# radio_module.net
KiCad netlist of a schematic drawn in EAGLE
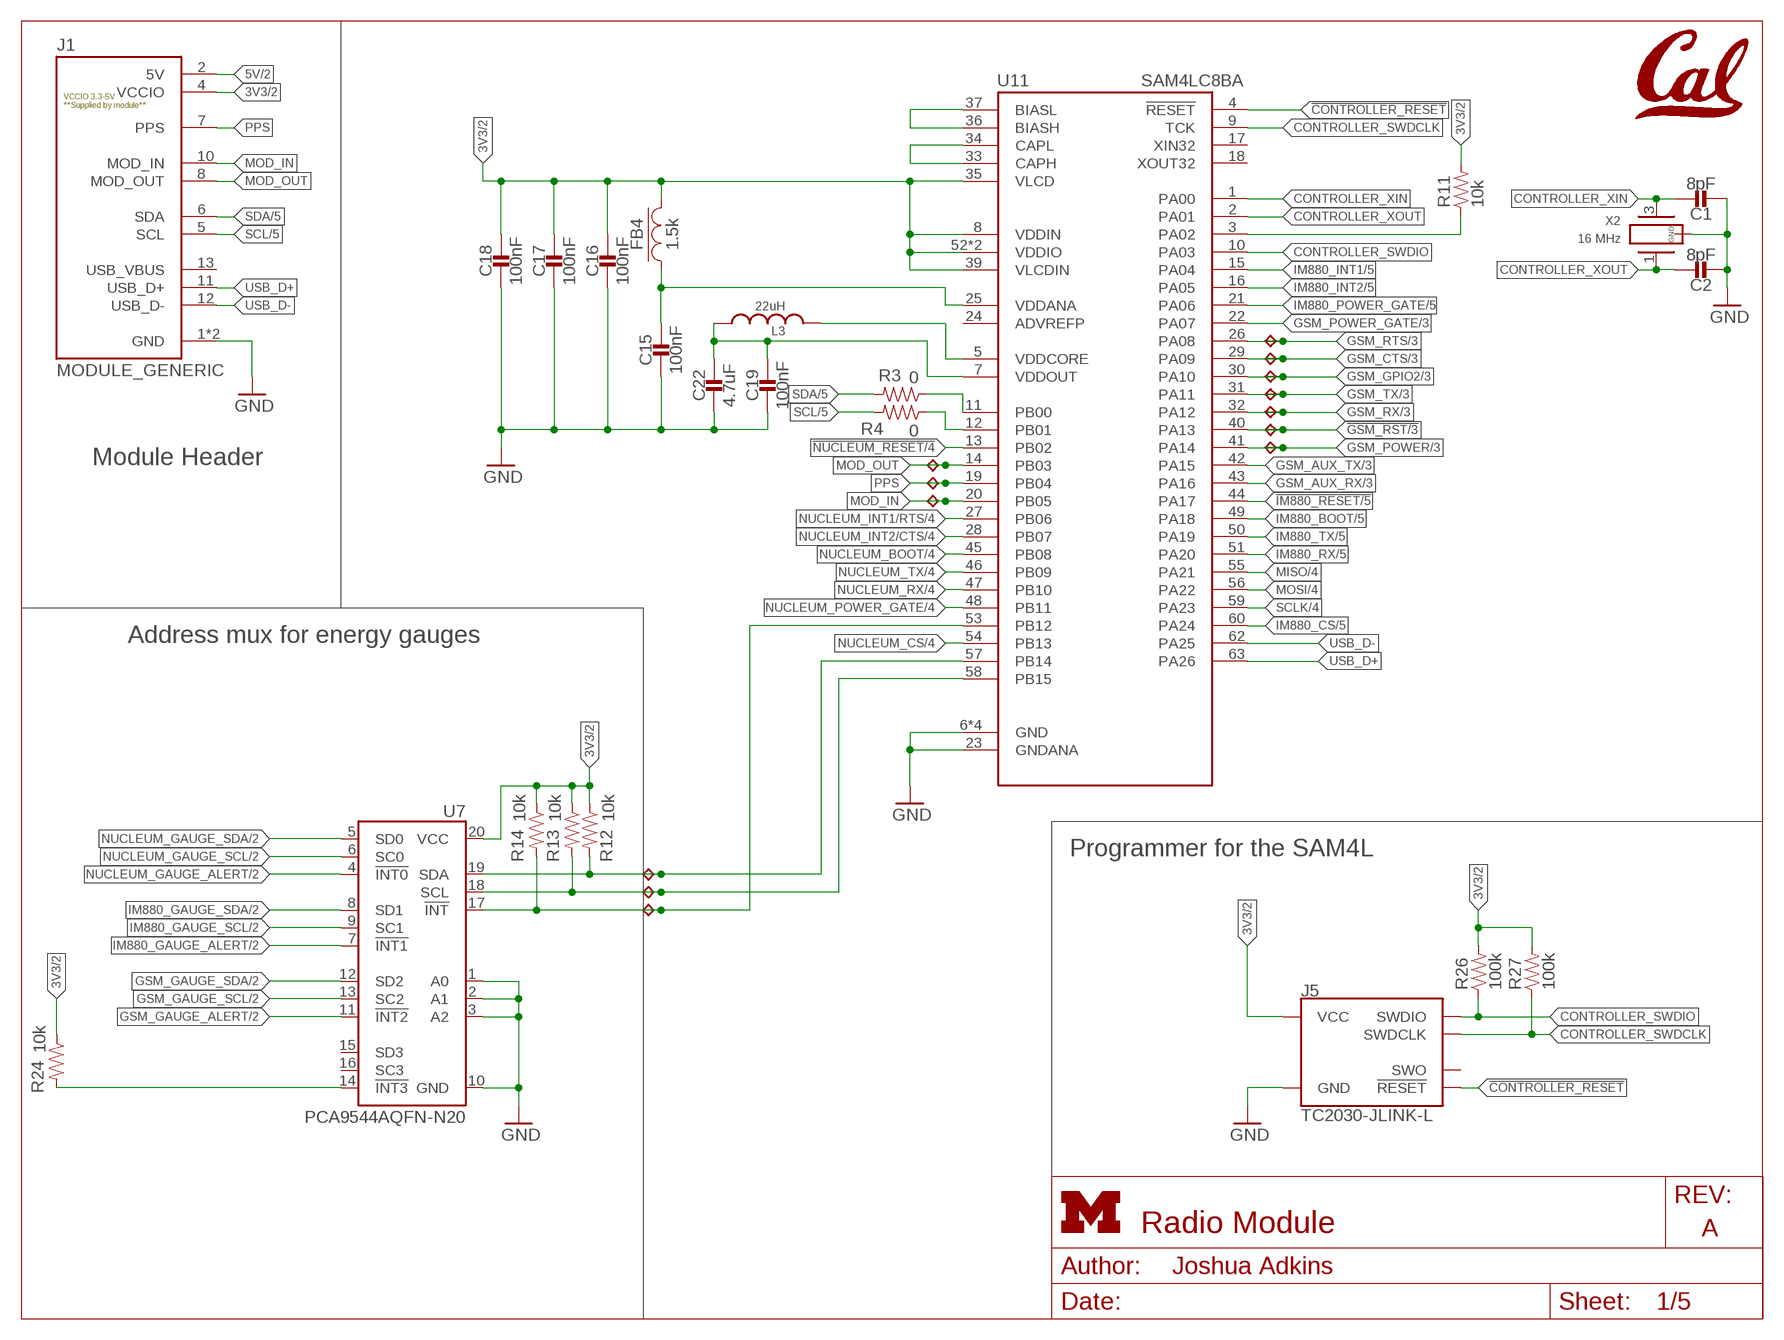
[diagram p0: schematic, sheet 1]
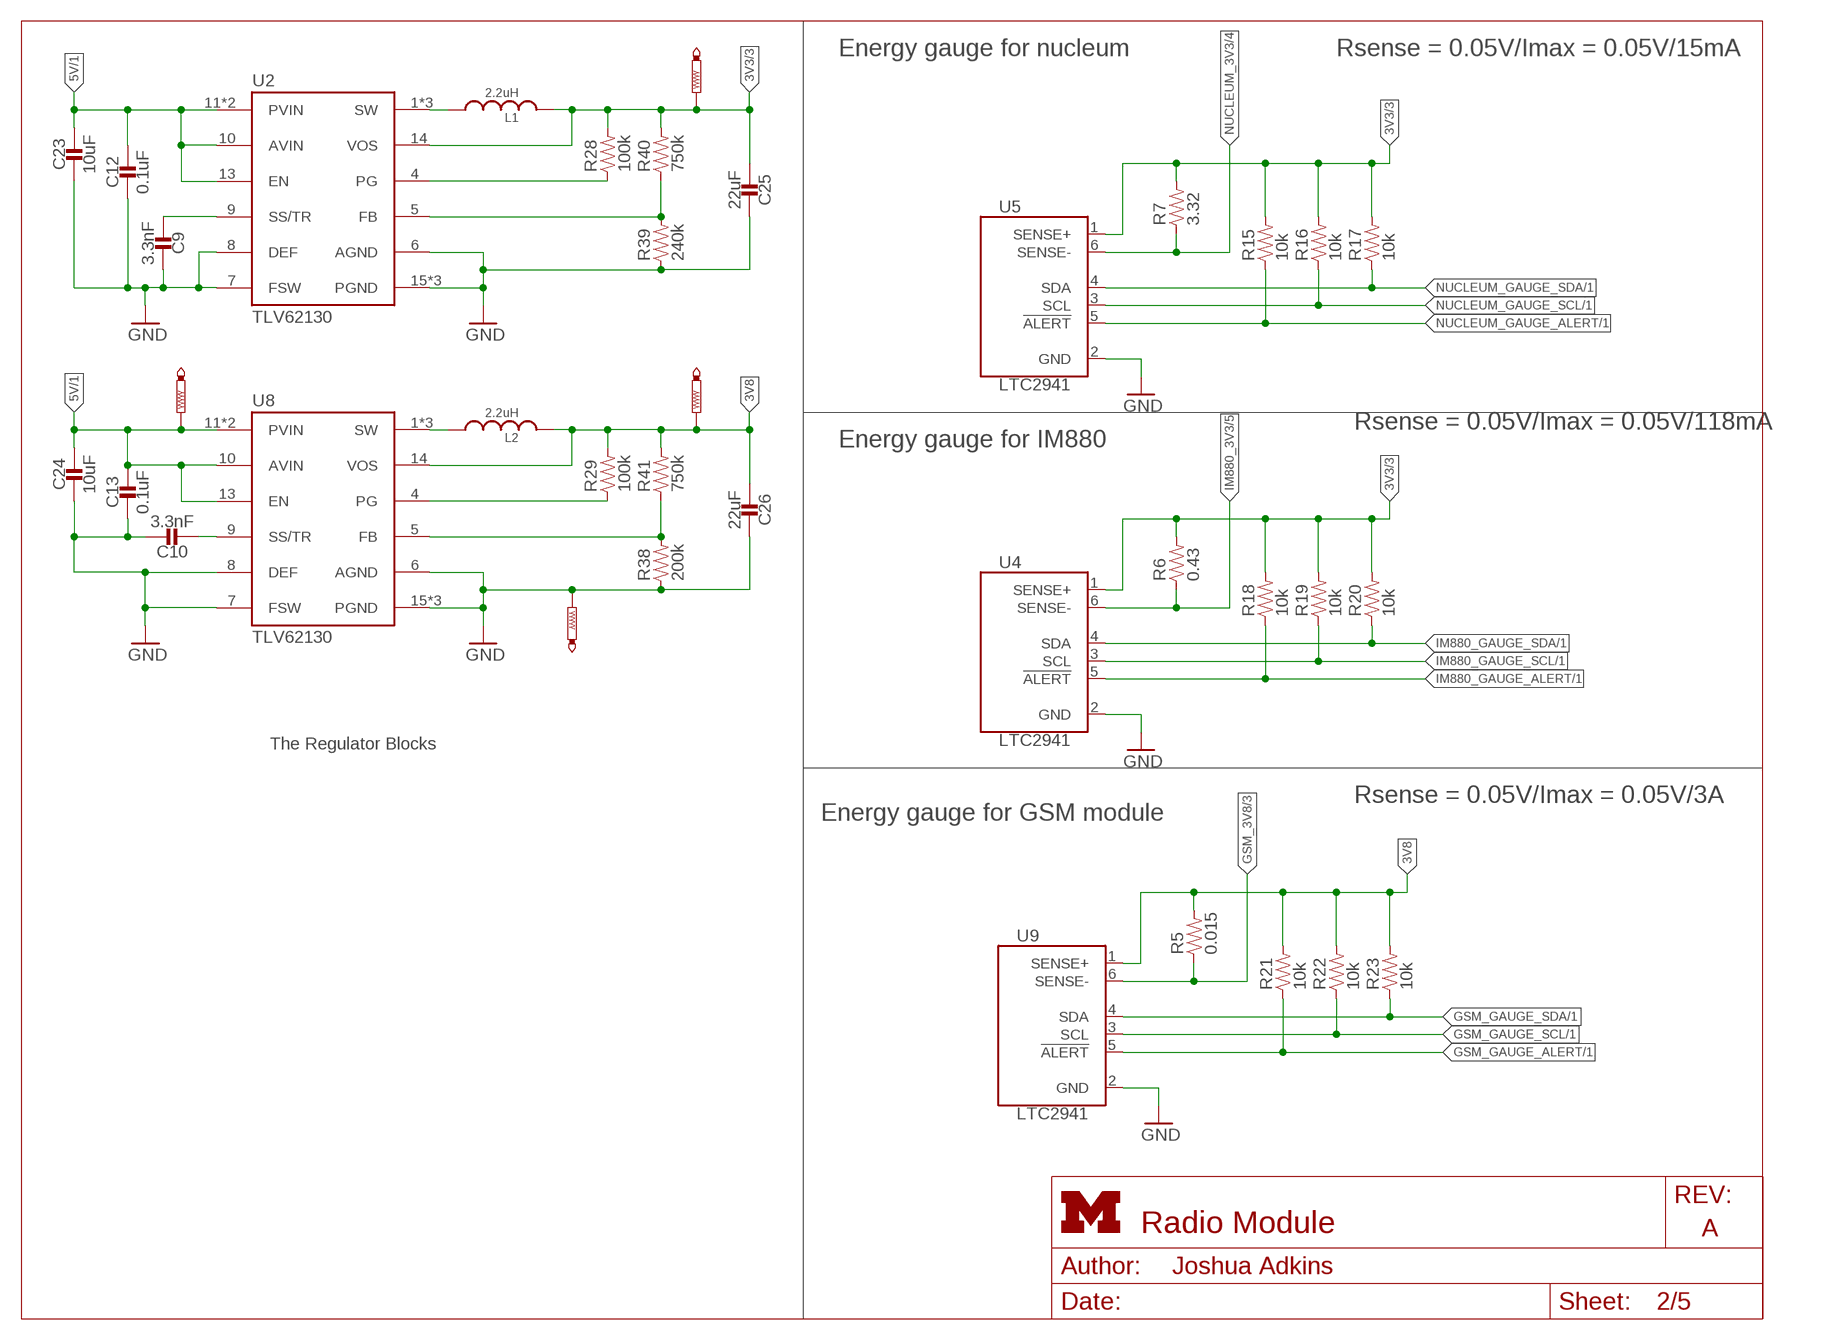
[diagram p1: schematic, sheet 2]
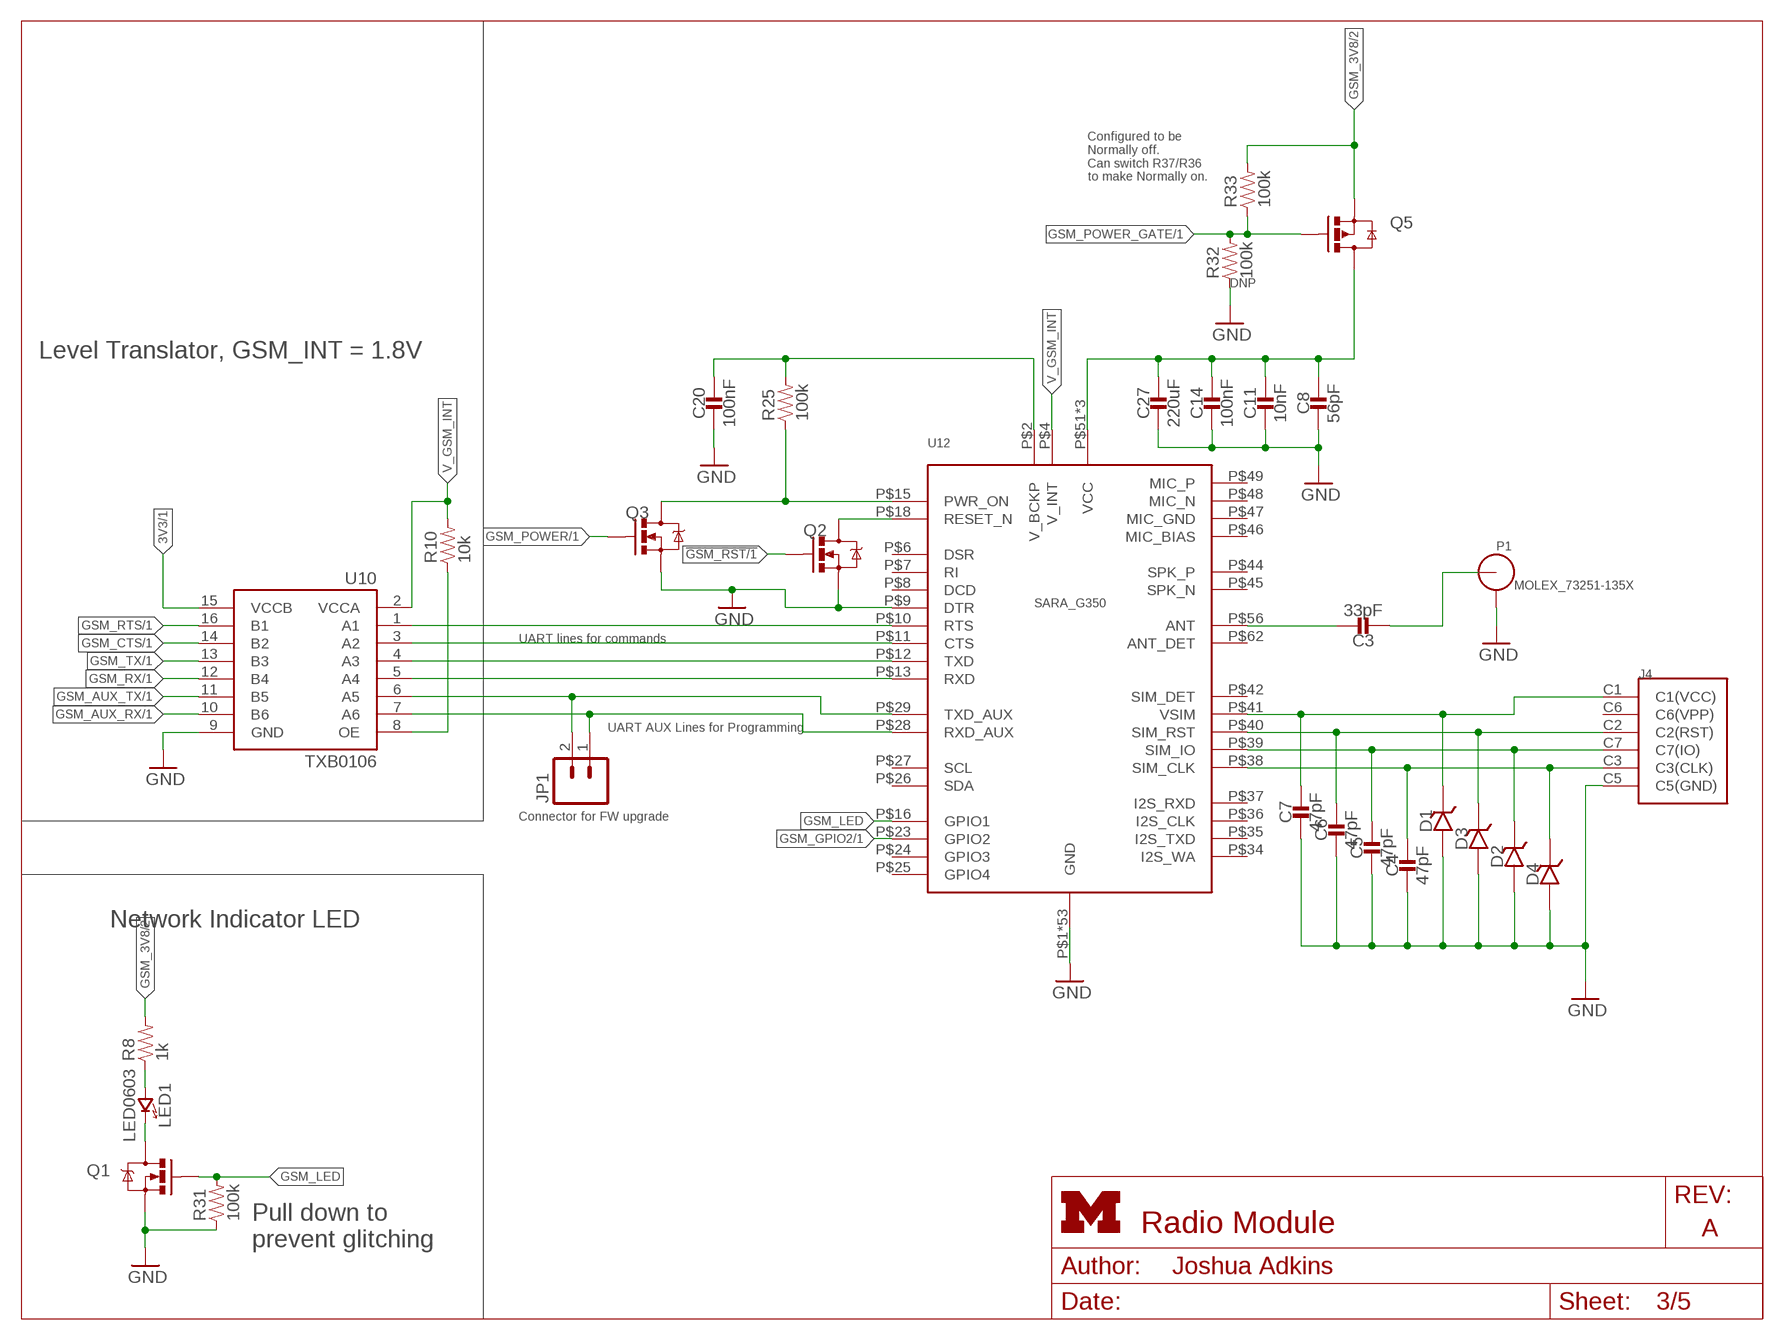
[diagram p2: schematic, sheet 3]
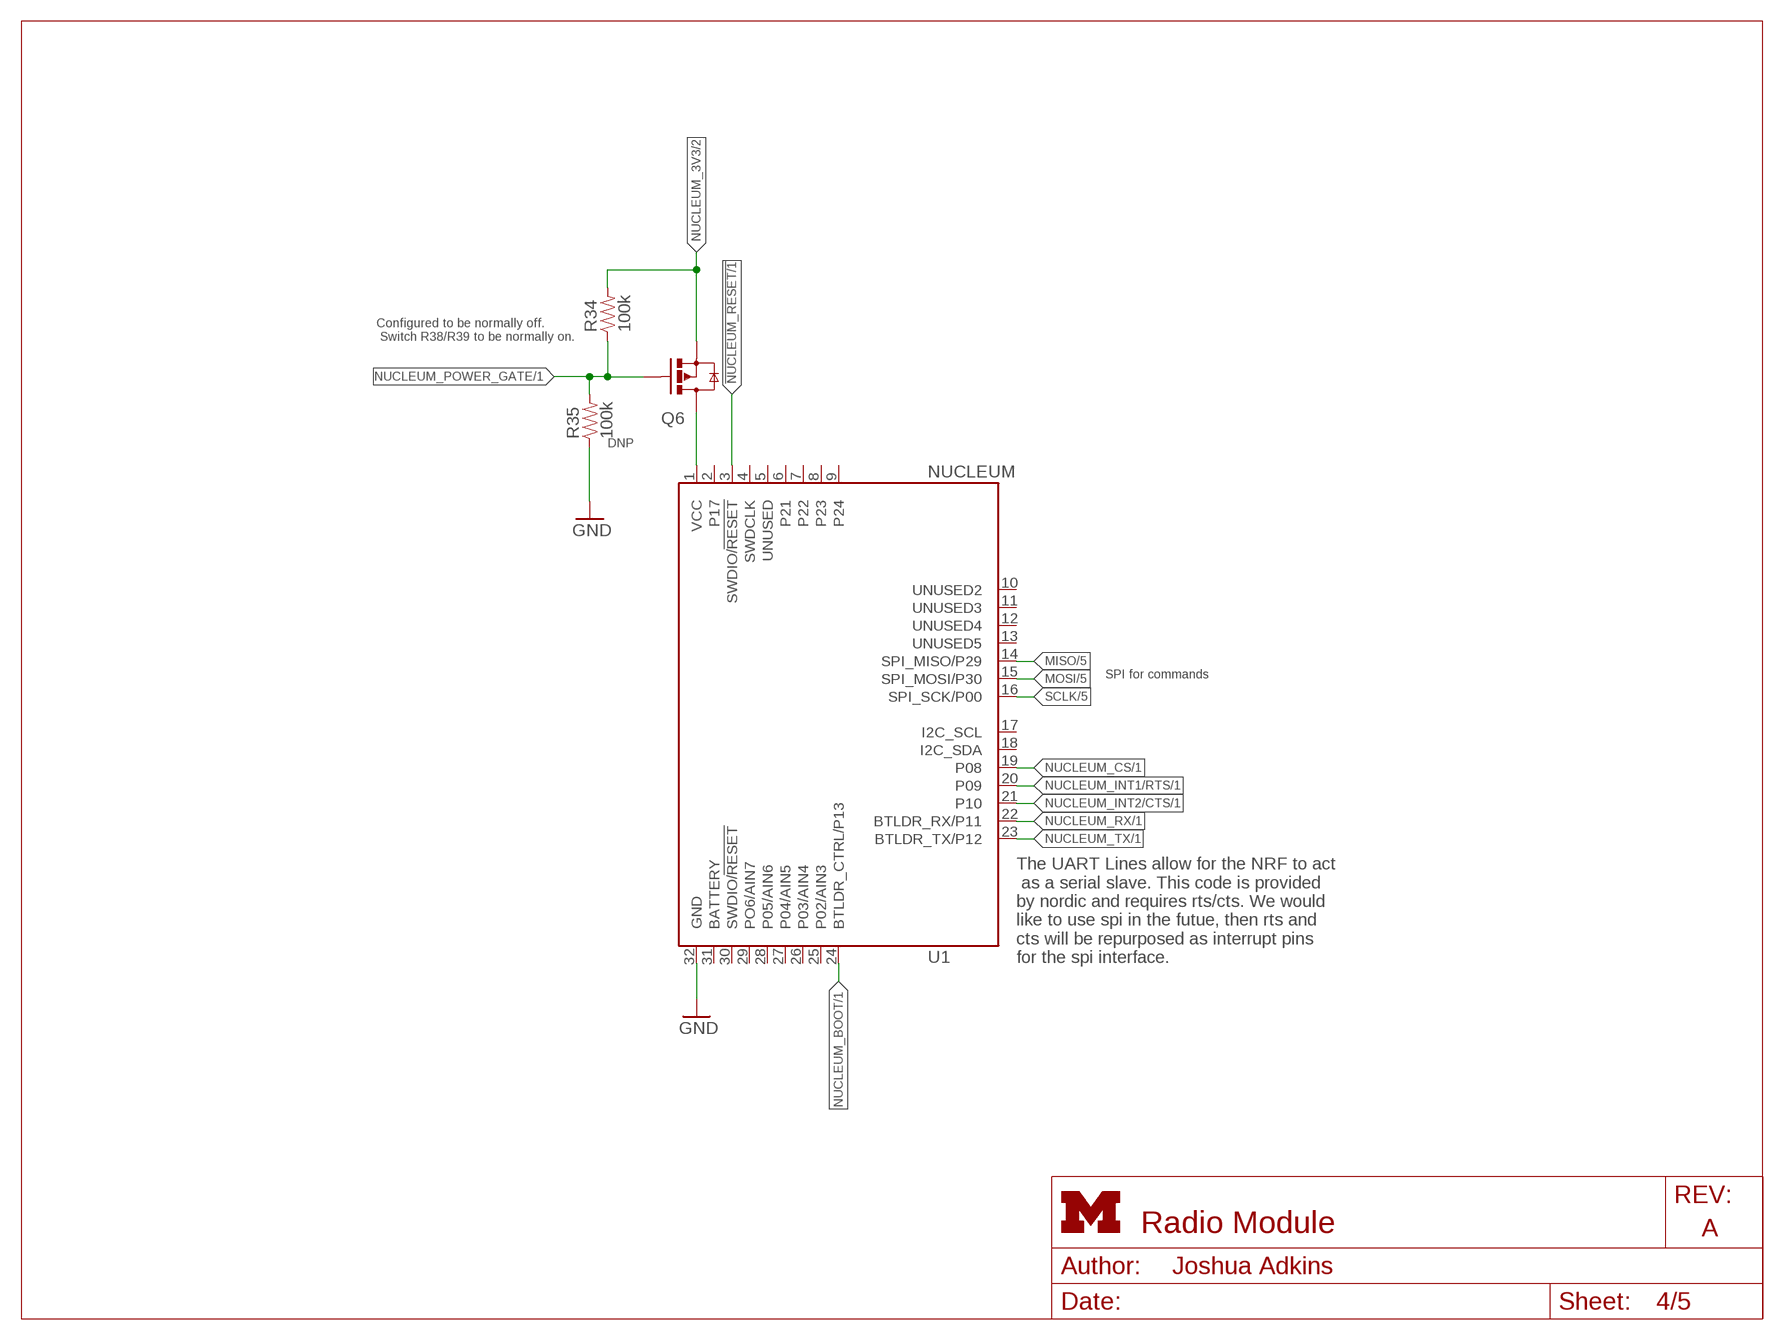
[diagram p3: schematic, sheet 4]
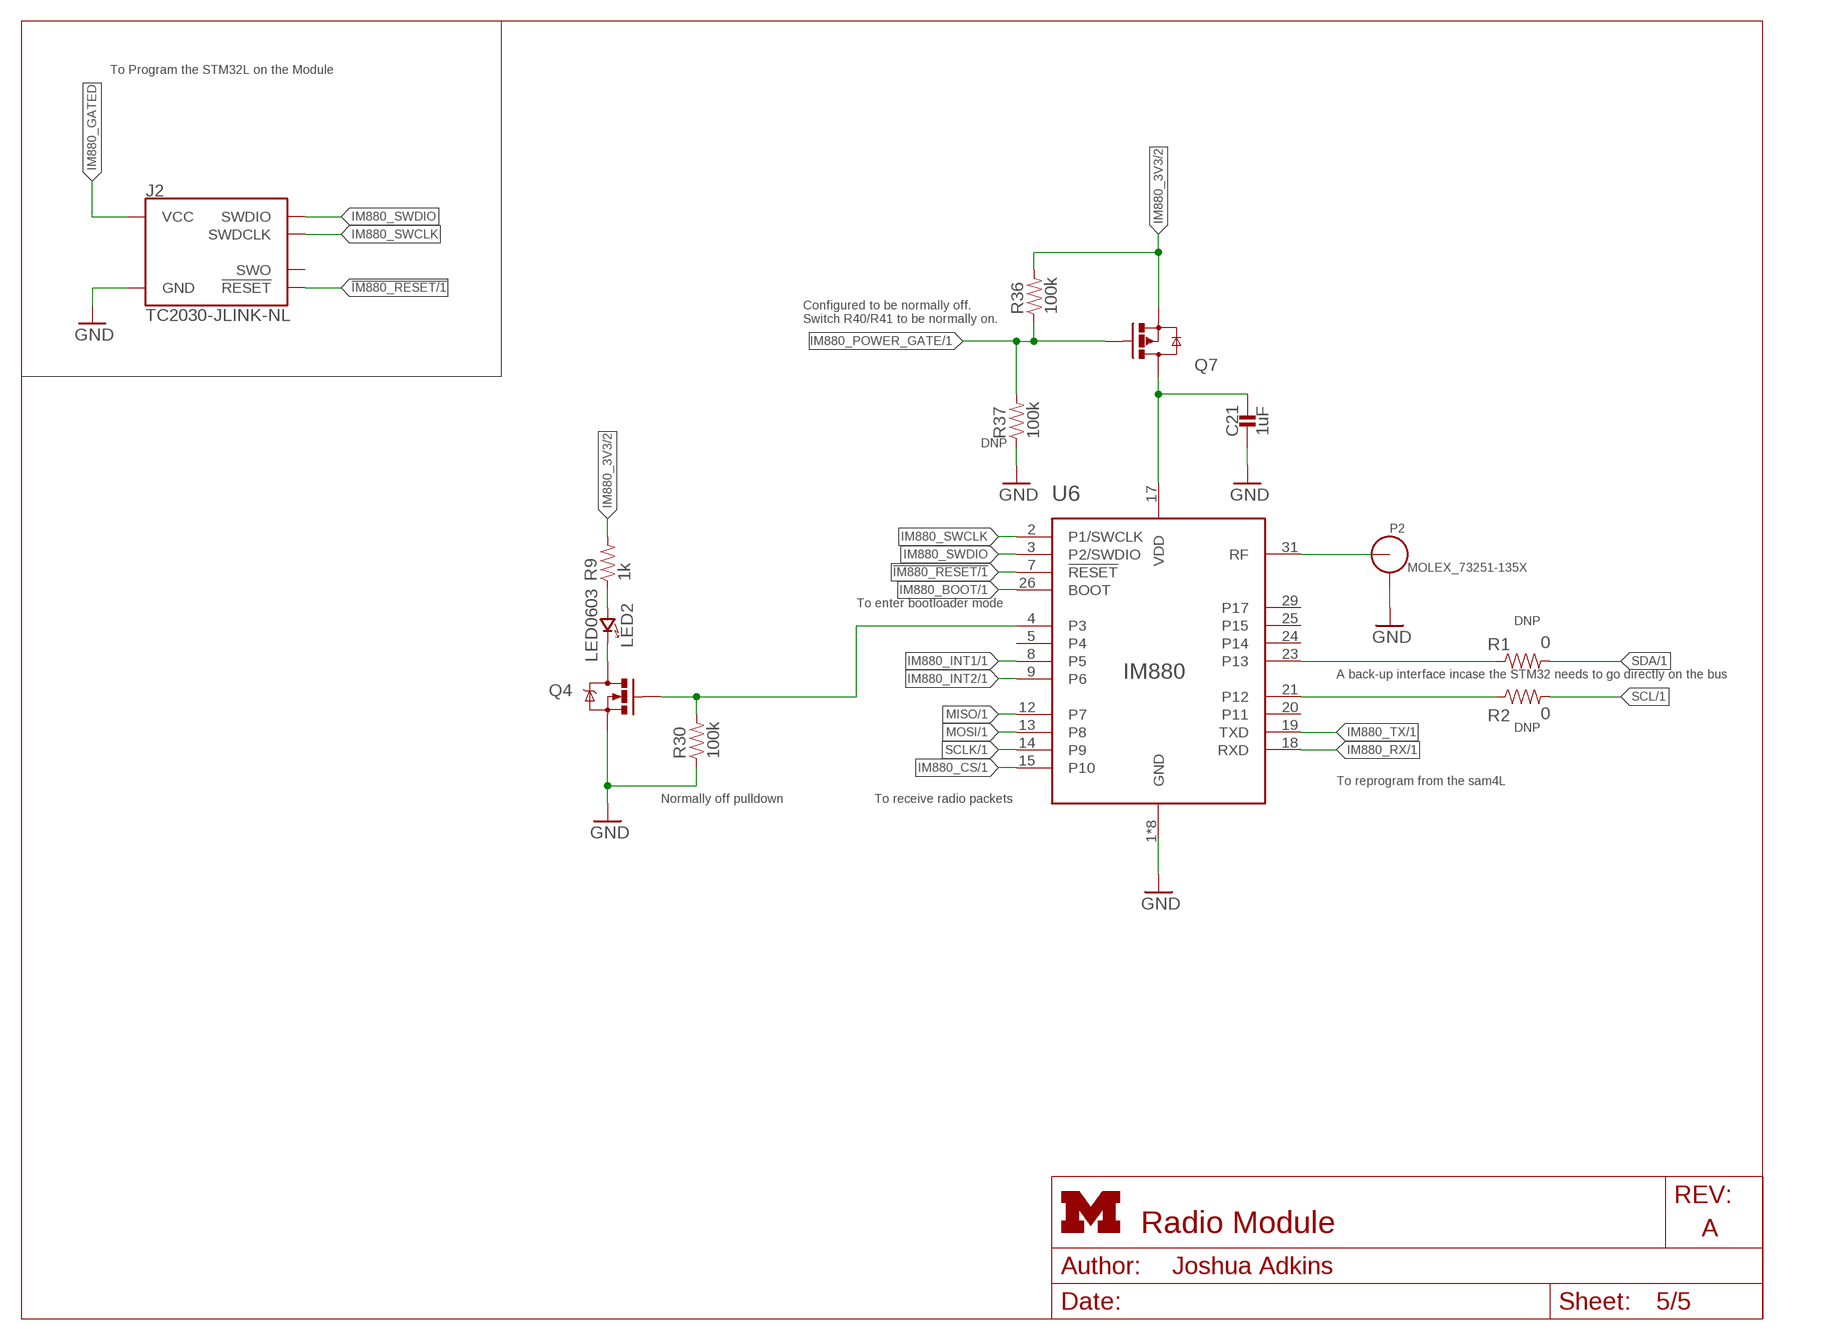
[diagram p4: schematic, sheet 5]

(export (version "E")
  (design (tool "Eeschema 10.0.6"))
  (components
    (comp (ref "C9")
      (value "3.3nF")
      (footprint "eagle-import:0402_CAP")
      (libsource (lib "eagle-import") (part "CAPACITOR0402_CAP"))
    )
    (comp (ref "C10")
      (value "3.3nF")
      (footprint "eagle-import:0402_CAP")
      (libsource (lib "eagle-import") (part "CAPACITOR0402_CAP"))
    )
    (comp (ref "C12")
      (value "0.1uF")
      (footprint "eagle-import:0402_CAP")
      (libsource (lib "eagle-import") (part "CAPACITOR0402_CAP"))
    )
    (comp (ref "C13")
      (value "0.1uF")
      (footprint "eagle-import:0402_CAP")
      (libsource (lib "eagle-import") (part "CAPACITOR0402_CAP"))
    )
    (comp (ref "C23")
      (value "10uF")
      (footprint "eagle-import:0402_CAP")
      (libsource (lib "eagle-import") (part "CAPACITOR0402_CAP"))
    )
    (comp (ref "C24")
      (value "10uF")
      (footprint "eagle-import:0402_CAP")
      (libsource (lib "eagle-import") (part "CAPACITOR0402_CAP"))
    )
    (comp (ref "C25")
      (value "22uF")
      (footprint "eagle-import:0402_CAP")
      (libsource (lib "eagle-import") (part "CAPACITOR0402_CAP"))
    )
    (comp (ref "C26")
      (value "22uF")
      (footprint "eagle-import:0402_CAP")
      (libsource (lib "eagle-import") (part "CAPACITOR0402_CAP"))
    )
    (comp (ref "L1")
      (value "2.2uH")
      (footprint "eagle-import:IHL-1212BZ-11")
      (libsource (lib "eagle-import") (part "INDUCTORIHL"))
    )
    (comp (ref "L2")
      (value "2.2uH")
      (footprint "eagle-import:IHL-1212BZ-11")
      (libsource (lib "eagle-import") (part "INDUCTORIHL"))
    )
    (comp (ref "R5")
      (value "0.015")
      (footprint "eagle-import:0603-RES")
      (libsource (lib "eagle-import") (part "RESISTOR0603_RES"))
    )
    (comp (ref "R6")
      (value "0.43")
      (footprint "eagle-import:0402_RES")
      (libsource (lib "eagle-import") (part "RESISTOR0402_RES"))
    )
    (comp (ref "R7")
      (value "3.32")
      (footprint "eagle-import:0402_RES")
      (libsource (lib "eagle-import") (part "RESISTOR0402_RES"))
    )
    (comp (ref "R15")
      (value "10k")
      (footprint "eagle-import:0402_RES")
      (libsource (lib "eagle-import") (part "RESISTOR0402_RES"))
    )
    (comp (ref "R16")
      (value "10k")
      (footprint "eagle-import:0402_RES")
      (libsource (lib "eagle-import") (part "RESISTOR0402_RES"))
    )
    (comp (ref "R17")
      (value "10k")
      (footprint "eagle-import:0402_RES")
      (libsource (lib "eagle-import") (part "RESISTOR0402_RES"))
    )
    (comp (ref "R18")
      (value "10k")
      (footprint "eagle-import:0402_RES")
      (libsource (lib "eagle-import") (part "RESISTOR0402_RES"))
    )
    (comp (ref "R19")
      (value "10k")
      (footprint "eagle-import:0402_RES")
      (libsource (lib "eagle-import") (part "RESISTOR0402_RES"))
    )
    (comp (ref "R20")
      (value "10k")
      (footprint "eagle-import:0402_RES")
      (libsource (lib "eagle-import") (part "RESISTOR0402_RES"))
    )
    (comp (ref "R21")
      (value "10k")
      (footprint "eagle-import:0402_RES")
      (libsource (lib "eagle-import") (part "RESISTOR0402_RES"))
    )
    (comp (ref "R22")
      (value "10k")
      (footprint "eagle-import:0402_RES")
      (libsource (lib "eagle-import") (part "RESISTOR0402_RES"))
    )
    (comp (ref "R23")
      (value "10k")
      (footprint "eagle-import:0402_RES")
      (libsource (lib "eagle-import") (part "RESISTOR0402_RES"))
    )
    (comp (ref "R28")
      (value "100k")
      (footprint "eagle-import:0402_RES")
      (libsource (lib "eagle-import") (part "RESISTOR0402_RES"))
    )
    (comp (ref "R29")
      (value "100k")
      (footprint "eagle-import:0402_RES")
      (libsource (lib "eagle-import") (part "RESISTOR0402_RES"))
    )
    (comp (ref "R38")
      (value "200k")
      (footprint "eagle-import:0402_RES")
      (libsource (lib "eagle-import") (part "RESISTOR0402_RES"))
    )
    (comp (ref "R39")
      (value "240k")
      (footprint "eagle-import:0402_RES")
      (libsource (lib "eagle-import") (part "RESISTOR0402_RES"))
    )
    (comp (ref "R40")
      (value "750k")
      (footprint "eagle-import:0402_RES")
      (libsource (lib "eagle-import") (part "RESISTOR0402_RES"))
    )
    (comp (ref "R41")
      (value "750k")
      (footprint "eagle-import:0402_RES")
      (libsource (lib "eagle-import") (part "RESISTOR0402_RES"))
    )
    (comp (ref "TP14")
      (value "PTR1PAD1-13")
      (footprint "eagle-import:P1-13")
      (libsource (lib "eagle-import") (part "PTR1PAD1-13"))
    )
    (comp (ref "TP15")
      (value "PTR1PAD1-13")
      (footprint "eagle-import:P1-13")
      (libsource (lib "eagle-import") (part "PTR1PAD1-13"))
    )
    (comp (ref "TP16")
      (value "PTR1PAD1-13")
      (footprint "eagle-import:P1-13")
      (libsource (lib "eagle-import") (part "PTR1PAD1-13"))
    )
    (comp (ref "TP17")
      (value "PTR1PAD1-13")
      (footprint "eagle-import:P1-13")
      (libsource (lib "eagle-import") (part "PTR1PAD1-13"))
    )
    (comp (ref "U2")
      (value "TLV62130")
      (footprint "eagle-import:TQFN-16_3MM")
      (libsource (lib "eagle-import") (part "TLV62130"))
    )
    (comp (ref "U4")
      (value "LTC2941")
      (footprint "eagle-import:DFN-6-2MMX3MM")
      (libsource (lib "eagle-import") (part "LTC2941"))
    )
    (comp (ref "U5")
      (value "LTC2941")
      (footprint "eagle-import:DFN-6-2MMX3MM")
      (libsource (lib "eagle-import") (part "LTC2941"))
    )
    (comp (ref "U8")
      (value "TLV62130")
      (footprint "eagle-import:TQFN-16_3MM")
      (libsource (lib "eagle-import") (part "TLV62130"))
    )
    (comp (ref "U9")
      (value "LTC2941")
      (footprint "eagle-import:DFN-6-2MMX3MM")
      (libsource (lib "eagle-import") (part "LTC2941"))
    )
    (comp (ref "C3")
      (value "33pF")
      (footprint "eagle-import:0603_CAP")
      (libsource (lib "eagle-import") (part "CAPACITOR0603_CAP"))
    )
    (comp (ref "C4")
      (value "47pF")
      (footprint "eagle-import:0402_CAP")
      (libsource (lib "eagle-import") (part "CAPACITOR0402_CAP"))
    )
    (comp (ref "C5")
      (value "47pF")
      (footprint "eagle-import:0402_CAP")
      (libsource (lib "eagle-import") (part "CAPACITOR0402_CAP"))
    )
    (comp (ref "C6")
      (value "47pF")
      (footprint "eagle-import:0402_CAP")
      (libsource (lib "eagle-import") (part "CAPACITOR0402_CAP"))
    )
    (comp (ref "C7")
      (value "47pF")
      (footprint "eagle-import:0402_CAP")
      (libsource (lib "eagle-import") (part "CAPACITOR0402_CAP"))
    )
    (comp (ref "C8")
      (value "56pF")
      (footprint "eagle-import:0402_CAP")
      (libsource (lib "eagle-import") (part "CAPACITOR0402_CAP"))
    )
    (comp (ref "C11")
      (value "10nF")
      (footprint "eagle-import:0402_CAP")
      (libsource (lib "eagle-import") (part "CAPACITOR0402_CAP"))
    )
    (comp (ref "C14")
      (value "100nF")
      (footprint "eagle-import:0402_CAP")
      (libsource (lib "eagle-import") (part "CAPACITOR0402_CAP"))
    )
    (comp (ref "C20")
      (value "100nF")
      (footprint "eagle-import:0402_CAP")
      (libsource (lib "eagle-import") (part "CAPACITOR0402_CAP"))
    )
    (comp (ref "C27")
      (value "220uF")
      (footprint "eagle-import:1210_CAP")
      (libsource (lib "eagle-import") (part "CAPACITOR1210_CAP"))
    )
    (comp (ref "D1")
      (value "14V")
      (footprint "eagle-import:0402_DIODE")
      (libsource (lib "eagle-import") (part "DIODE_ZENER"))
    )
    (comp (ref "D2")
      (value "DIODE_ZENER")
      (footprint "eagle-import:0402_DIODE")
      (libsource (lib "eagle-import") (part "DIODE_ZENER"))
    )
    (comp (ref "D3")
      (value "DIODE_ZENER")
      (footprint "eagle-import:0402_DIODE")
      (libsource (lib "eagle-import") (part "DIODE_ZENER"))
    )
    (comp (ref "D4")
      (value "DIODE_ZENER")
      (footprint "eagle-import:0402_DIODE")
      (libsource (lib "eagle-import") (part "DIODE_ZENER"))
    )
    (comp (ref "J4")
      (value "NANO_SIM")
      (footprint "eagle-import:WURTH_NANO_SIM")
      (libsource (lib "eagle-import") (part "NANO_SIM"))
    )
    (comp (ref "JP1")
      (value "M02PTH")
      (footprint "eagle-import:1X02")
      (libsource (lib "eagle-import") (part "M02PTH"))
    )
    (comp (ref "LED1")
      (value "LED0603")
      (footprint "eagle-import:LED-0603")
      (libsource (lib "eagle-import") (part "LED0603"))
    )
    (comp (ref "P1")
      (value "MOLEX_73251-135X")
      (footprint "eagle-import:SMA-J_PCB")
      (libsource (lib "eagle-import") (part "MOLEX_73251-135X"))
    )
    (comp (ref "Q1")
      (value "MOSFET-NCHANNELXFDN-3")
      (footprint "eagle-import:XFDFN-3")
      (libsource (lib "eagle-import") (part "MOSFET-NCHANNELXFDN-3"))
    )
    (comp (ref "Q2")
      (value "MOSFET-NCHANNELXFDN-3")
      (footprint "eagle-import:XFDFN-3")
      (libsource (lib "eagle-import") (part "MOSFET-NCHANNELXFDN-3"))
    )
    (comp (ref "Q3")
      (value "MOSFET-NCHANNELXFDN-3")
      (footprint "eagle-import:XFDFN-3")
      (libsource (lib "eagle-import") (part "MOSFET-NCHANNELXFDN-3"))
    )
    (comp (ref "Q5")
      (value "SI223DDS")
      (footprint "eagle-import:SOT23-3")
      (libsource (lib "eagle-import") (part "SI223DDS"))
    )
    (comp (ref "R8")
      (value "1k")
      (footprint "eagle-import:0402_RES")
      (libsource (lib "eagle-import") (part "RESISTOR0402_RES"))
    )
    (comp (ref "R10")
      (value "10k")
      (footprint "eagle-import:0402_RES")
      (libsource (lib "eagle-import") (part "RESISTOR0402_RES"))
    )
    (comp (ref "R25")
      (value "100k")
      (footprint "eagle-import:0402_RES")
      (libsource (lib "eagle-import") (part "RESISTOR0402_RES"))
    )
    (comp (ref "R31")
      (value "100k")
      (footprint "eagle-import:0402_RES")
      (libsource (lib "eagle-import") (part "RESISTOR0402_RES"))
    )
    (comp (ref "R32")
      (value "100k")
      (footprint "eagle-import:0402_RES")
      (libsource (lib "eagle-import") (part "RESISTOR0402_RES"))
    )
    (comp (ref "R33")
      (value "100k")
      (footprint "eagle-import:0402_RES")
      (libsource (lib "eagle-import") (part "RESISTOR0402_RES"))
    )
    (comp (ref "U10")
      (value "TXB0106")
      (footprint "eagle-import:R-PVQFN-N16")
      (libsource (lib "eagle-import") (part "TXB0106"))
    )
    (comp (ref "U12")
      (value "UBLOX_SARA_G350")
      (footprint "eagle-import:UBLOX_SARA_G3")
      (libsource (lib "eagle-import") (part "UBLOX_SARA_G350"))
    )
    (comp (ref "C21")
      (value "1uF")
      (footprint "eagle-import:0402_CAP")
      (libsource (lib "eagle-import") (part "CAPACITOR0402_CAP"))
    )
    (comp (ref "J2")
      (value "TC2030-JLINK-NL")
      (footprint "eagle-import:TC2030-IDC-NL")
      (libsource (lib "eagle-import") (part "TC2030-JLINK-NL"))
    )
    (comp (ref "LED2")
      (value "LED0603")
      (footprint "eagle-import:LED-0603")
      (libsource (lib "eagle-import") (part "LED0603"))
    )
    (comp (ref "P2")
      (value "MOLEX_73251-135X")
      (footprint "eagle-import:SMA-J_PCB")
      (libsource (lib "eagle-import") (part "MOLEX_73251-135X"))
    )
    (comp (ref "Q4")
      (value "MOSFET-NCHANNELXFDN-3")
      (footprint "eagle-import:XFDFN-3")
      (libsource (lib "eagle-import") (part "MOSFET-NCHANNELXFDN-3"))
    )
    (comp (ref "Q7")
      (value "SI223DDS")
      (footprint "eagle-import:SOT23-3")
      (libsource (lib "eagle-import") (part "SI223DDS"))
    )
    (comp (ref "R1")
      (value "0")
      (footprint "eagle-import:0402_RES")
      (libsource (lib "eagle-import") (part "RESISTOR0402_RES"))
    )
    (comp (ref "R2")
      (value "0")
      (footprint "eagle-import:0402_RES")
      (libsource (lib "eagle-import") (part "RESISTOR0402_RES"))
    )
    (comp (ref "R9")
      (value "1k")
      (footprint "eagle-import:0402_RES")
      (libsource (lib "eagle-import") (part "RESISTOR0402_RES"))
    )
    (comp (ref "R30")
      (value "100k")
      (footprint "eagle-import:0402_RES")
      (libsource (lib "eagle-import") (part "RESISTOR0402_RES"))
    )
    (comp (ref "R36")
      (value "100k")
      (footprint "eagle-import:0402_RES")
      (libsource (lib "eagle-import") (part "RESISTOR0402_RES"))
    )
    (comp (ref "R37")
      (value "100k")
      (footprint "eagle-import:0402_RES")
      (libsource (lib "eagle-import") (part "RESISTOR0402_RES"))
    )
    (comp (ref "U6")
      (value "IM880_MODULE")
      (footprint "eagle-import:IM880_MODULE")
      (libsource (lib "eagle-import") (part "IM880_MODULE"))
    )
    (comp (ref "Q6")
      (value "SI223DDS")
      (footprint "eagle-import:SOT23-3")
      (libsource (lib "eagle-import") (part "SI223DDS"))
    )
    (comp (ref "R34")
      (value "100k")
      (footprint "eagle-import:0402_RES")
      (libsource (lib "eagle-import") (part "RESISTOR0402_RES"))
    )
    (comp (ref "R35")
      (value "100k")
      (footprint "eagle-import:0402_RES")
      (libsource (lib "eagle-import") (part "RESISTOR0402_RES"))
    )
    (comp (ref "U1")
      (value "NUCLEUM")
      (footprint "eagle-import:NUCLEUM")
      (libsource (lib "eagle-import") (part "NUCLEUM"))
    )
    (comp (ref "C1")
      (value "8pF")
      (footprint "eagle-import:0402_CAP")
      (libsource (lib "eagle-import") (part "CAPACITOR0402_CAP"))
    )
    (comp (ref "C2")
      (value "8pF")
      (footprint "eagle-import:0402_CAP")
      (libsource (lib "eagle-import") (part "CAPACITOR0402_CAP"))
    )
    (comp (ref "C15")
      (value "100nF")
      (footprint "eagle-import:0402_CAP")
      (libsource (lib "eagle-import") (part "CAPACITOR0402_CAP"))
    )
    (comp (ref "C16")
      (value "100nF")
      (footprint "eagle-import:0402_CAP")
      (libsource (lib "eagle-import") (part "CAPACITOR0402_CAP"))
    )
    (comp (ref "C17")
      (value "100nF")
      (footprint "eagle-import:0402_CAP")
      (libsource (lib "eagle-import") (part "CAPACITOR0402_CAP"))
    )
    (comp (ref "C18")
      (value "100nF")
      (footprint "eagle-import:0402_CAP")
      (libsource (lib "eagle-import") (part "CAPACITOR0402_CAP"))
    )
    (comp (ref "C19")
      (value "100nF")
      (footprint "eagle-import:0402_CAP")
      (libsource (lib "eagle-import") (part "CAPACITOR0402_CAP"))
    )
    (comp (ref "C22")
      (value "4.7uF")
      (footprint "eagle-import:0402_CAP")
      (libsource (lib "eagle-import") (part "CAPACITOR0402_CAP"))
    )
    (comp (ref "FB4")
      (value "1.5k")
      (footprint "eagle-import:0402_CAP")
      (libsource (lib "eagle-import") (part "FERRITE_BEAD0402"))
    )
    (comp (ref "J1")
      (value "MODULE_GENERIC")
      (footprint "eagle-import:MODULE_GENERIC")
      (libsource (lib "eagle-import") (part "MODULE_GENERIC"))
    )
    (comp (ref "J5")
      (value "TC2030-JLINK-L")
      (footprint "eagle-import:TC2030-IDC")
      (libsource (lib "eagle-import") (part "TC2030-JLINK-L"))
    )
    (comp (ref "L3")
      (value "22uH")
      (footprint "eagle-import:1212")
      (libsource (lib "eagle-import") (part "LHQ3NP"))
    )
    (comp (ref "R3")
      (value "0")
      (footprint "eagle-import:0402_RES")
      (libsource (lib "eagle-import") (part "RESISTOR0402_RES"))
    )
    (comp (ref "R4")
      (value "0")
      (footprint "eagle-import:0402_RES")
      (libsource (lib "eagle-import") (part "RESISTOR0402_RES"))
    )
    (comp (ref "R11")
      (value "10k")
      (footprint "eagle-import:0402_RES")
      (libsource (lib "eagle-import") (part "RESISTOR0402_RES"))
    )
    (comp (ref "R12")
      (value "10k")
      (footprint "eagle-import:0402_RES")
      (libsource (lib "eagle-import") (part "RESISTOR0402_RES"))
    )
    (comp (ref "R13")
      (value "10k")
      (footprint "eagle-import:0402_RES")
      (libsource (lib "eagle-import") (part "RESISTOR0402_RES"))
    )
    (comp (ref "R14")
      (value "10k")
      (footprint "eagle-import:0402_RES")
      (libsource (lib "eagle-import") (part "RESISTOR0402_RES"))
    )
    (comp (ref "R24")
      (value "10k")
      (footprint "eagle-import:0402_RES")
      (libsource (lib "eagle-import") (part "RESISTOR0402_RES"))
    )
    (comp (ref "R26")
      (value "100k")
      (footprint "eagle-import:0402_RES")
      (libsource (lib "eagle-import") (part "RESISTOR0402_RES"))
    )
    (comp (ref "R27")
      (value "100k")
      (footprint "eagle-import:0402_RES")
      (libsource (lib "eagle-import") (part "RESISTOR0402_RES"))
    )
    (comp (ref "TP1")
      (value "TPB1,27")
      (footprint "eagle-import:B1,27")
      (libsource (lib "eagle-import") (part "TPB1,27"))
    )
    (comp (ref "TP2")
      (value "TPB1,27")
      (footprint "eagle-import:B1,27")
      (libsource (lib "eagle-import") (part "TPB1,27"))
    )
    (comp (ref "TP3")
      (value "TPB1,27")
      (footprint "eagle-import:B1,27")
      (libsource (lib "eagle-import") (part "TPB1,27"))
    )
    (comp (ref "TP4")
      (value "TPB1,27")
      (footprint "eagle-import:B1,27")
      (libsource (lib "eagle-import") (part "TPB1,27"))
    )
    (comp (ref "TP5")
      (value "TPB1,27")
      (footprint "eagle-import:B1,27")
      (libsource (lib "eagle-import") (part "TPB1,27"))
    )
    (comp (ref "TP6")
      (value "TPB1,27")
      (footprint "eagle-import:B1,27")
      (libsource (lib "eagle-import") (part "TPB1,27"))
    )
    (comp (ref "TP7")
      (value "TPB1,27")
      (footprint "eagle-import:B1,27")
      (libsource (lib "eagle-import") (part "TPB1,27"))
    )
    (comp (ref "TP8")
      (value "TPB1,27")
      (footprint "eagle-import:B1,27")
      (libsource (lib "eagle-import") (part "TPB1,27"))
    )
    (comp (ref "TP9")
      (value "TPB1,27")
      (footprint "eagle-import:B1,27")
      (libsource (lib "eagle-import") (part "TPB1,27"))
    )
    (comp (ref "TP10")
      (value "TPB1,27")
      (footprint "eagle-import:B1,27")
      (libsource (lib "eagle-import") (part "TPB1,27"))
    )
    (comp (ref "TP11")
      (value "TPB1,27")
      (footprint "eagle-import:B1,27")
      (libsource (lib "eagle-import") (part "TPB1,27"))
    )
    (comp (ref "TP12")
      (value "TPB1,27")
      (footprint "eagle-import:B1,27")
      (libsource (lib "eagle-import") (part "TPB1,27"))
    )
    (comp (ref "TP13")
      (value "TPB1,27")
      (footprint "eagle-import:B1,27")
      (libsource (lib "eagle-import") (part "TPB1,27"))
    )
    (comp (ref "U$1")
      (value "UCB_CAL100MIL")
      (footprint "eagle-import:UCB_CAL_100MIL")
      (libsource (lib "eagle-import") (part "UCB_CAL100MIL"))
    )
    (comp (ref "U7")
      (value "PCA9544AQFN-N20")
      (footprint "eagle-import:QFN-N20")
      (libsource (lib "eagle-import") (part "PCA9544AQFN-N20"))
    )
    (comp (ref "U11")
      (value "SAM4LC8BA")
      (footprint "eagle-import:QFN-64-9MM")
      (libsource (lib "eagle-import") (part "SAM4LC8BA"))
    )
    (comp (ref "X2")
      (value "16 MHz")
      (footprint "eagle-import:FHXXX")
      (libsource (lib "eagle-import") (part "FH1600015"))
    )
  )
  (nets
    (net (code "1") (name "3V3") (class "Default")
      (node (ref "C16") (pin "1") (pinfunction "1_1") (pintype "bidirectional"))
      (node (ref "C17") (pin "1") (pinfunction "1_1") (pintype "bidirectional"))
      (node (ref "C18") (pin "1") (pinfunction "1_1") (pintype "bidirectional"))
      (node (ref "C25") (pin "2") (pinfunction "2_2") (pintype "bidirectional"))
      (node (ref "FB4") (pin "2") (pinfunction "P$2_2") (pintype "bidirectional"))
      (node (ref "J1") (pin "4") (pinfunction "VCCIO_4") (pintype "bidirectional"))
      (node (ref "J5") (pin "1") (pinfunction "VCC_1") (pintype "bidirectional"))
      (node (ref "L1") (pin "P$2") (pinfunction "2_P$2") (pintype "bidirectional"))
      (node (ref "R11") (pin "2") (pinfunction "2_2") (pintype "passive"))
      (node (ref "R12") (pin "1") (pinfunction "1_1") (pintype "passive"))
      (node (ref "R13") (pin "1") (pinfunction "1_1") (pintype "passive"))
      (node (ref "R14") (pin "1") (pinfunction "1_1") (pintype "passive"))
      (node (ref "R15") (pin "2") (pinfunction "2_2") (pintype "passive"))
      (node (ref "R16") (pin "2") (pinfunction "2_2") (pintype "passive"))
      (node (ref "R17") (pin "2") (pinfunction "2_2") (pintype "passive"))
      (node (ref "R18") (pin "2") (pinfunction "2_2") (pintype "passive"))
      (node (ref "R19") (pin "2") (pinfunction "2_2") (pintype "passive"))
      (node (ref "R20") (pin "2") (pinfunction "2_2") (pintype "passive"))
      (node (ref "R24") (pin "1") (pinfunction "1_1") (pintype "passive"))
      (node (ref "R26") (pin "2") (pinfunction "2_2") (pintype "passive"))
      (node (ref "R27") (pin "2") (pinfunction "2_2") (pintype "passive"))
      (node (ref "R28") (pin "2") (pinfunction "2_2") (pintype "passive"))
      (node (ref "R40") (pin "2") (pinfunction "2_2") (pintype "passive"))
      (node (ref "R6") (pin "2") (pinfunction "2_2") (pintype "passive"))
      (node (ref "R7") (pin "2") (pinfunction "2_2") (pintype "passive"))
      (node (ref "TP17") (pin "TP") (pinfunction "TP_TP") (pintype "input"))
      (node (ref "U10") (pin "15") (pinfunction "VCCB_15") (pintype "bidirectional"))
      (node (ref "U11") (pin "35") (pinfunction "VLCD_35") (pintype "bidirectional"))
      (node (ref "U11") (pin "39") (pinfunction "VLCDIN_39") (pintype "power_in"))
      (node (ref "U11") (pin "52") (pinfunction "VDDIO_52") (pintype "power_in"))
      (node (ref "U11") (pin "61") (pinfunction "VDDIO_61") (pintype "power_in"))
      (node (ref "U11") (pin "8") (pinfunction "VDDIN_8") (pintype "power_in"))
      (node (ref "U2") (pin "14") (pinfunction "VOS_14") (pintype "bidirectional"))
      (node (ref "U4") (pin "1") (pinfunction "SENSE+_1") (pintype "open_collector"))
      (node (ref "U5") (pin "1") (pinfunction "SENSE+_1") (pintype "open_collector"))
      (node (ref "U7") (pin "20") (pinfunction "VCC_20") (pintype "bidirectional"))
    )
    (net (code "2") (name "3V8") (class "Default")
      (node (ref "C26") (pin "2") (pinfunction "2_2") (pintype "bidirectional"))
      (node (ref "L2") (pin "P$2") (pinfunction "2_P$2") (pintype "bidirectional"))
      (node (ref "R21") (pin "2") (pinfunction "2_2") (pintype "passive"))
      (node (ref "R22") (pin "2") (pinfunction "2_2") (pintype "passive"))
      (node (ref "R23") (pin "2") (pinfunction "2_2") (pintype "passive"))
      (node (ref "R29") (pin "2") (pinfunction "2_2") (pintype "passive"))
      (node (ref "R41") (pin "2") (pinfunction "2_2") (pintype "passive"))
      (node (ref "R5") (pin "2") (pinfunction "2_2") (pintype "passive"))
      (node (ref "TP14") (pin "TP") (pinfunction "TP_TP") (pintype "input"))
      (node (ref "U8") (pin "14") (pinfunction "VOS_14") (pintype "bidirectional"))
      (node (ref "U9") (pin "1") (pinfunction "SENSE+_1") (pintype "open_collector"))
    )
    (net (code "3") (name "5V") (class "Default")
      (node (ref "C12") (pin "1") (pinfunction "1_1") (pintype "bidirectional"))
      (node (ref "C13") (pin "1") (pinfunction "1_1") (pintype "bidirectional"))
      (node (ref "C23") (pin "1") (pinfunction "1_1") (pintype "bidirectional"))
      (node (ref "C24") (pin "1") (pinfunction "1_1") (pintype "bidirectional"))
      (node (ref "J1") (pin "2") (pinfunction "5V_2") (pintype "bidirectional"))
      (node (ref "TP16") (pin "TP") (pinfunction "TP_TP") (pintype "input"))
      (node (ref "U2") (pin "10") (pinfunction "AVIN_10") (pintype "bidirectional"))
      (node (ref "U2") (pin "11") (pinfunction "PVIN_11") (pintype "bidirectional"))
      (node (ref "U2") (pin "12") (pinfunction "PVIN_12") (pintype "bidirectional"))
      (node (ref "U2") (pin "13") (pinfunction "EN_13") (pintype "bidirectional"))
      (node (ref "U8") (pin "10") (pinfunction "AVIN_10") (pintype "bidirectional"))
      (node (ref "U8") (pin "11") (pinfunction "PVIN_11") (pintype "bidirectional"))
      (node (ref "U8") (pin "12") (pinfunction "PVIN_12") (pintype "bidirectional"))
      (node (ref "U8") (pin "13") (pinfunction "EN_13") (pintype "bidirectional"))
    )
    (net (code "4") (name "ADVREFP") (class "Default")
      (node (ref "U11") (pin "24") (pinfunction "ADVREFP_24") (pintype "power_in"))
    )
    (net (code "5") (name "CONTROLLER_SWDCLK") (class "Default")
      (node (ref "J5") (pin "4") (pinfunction "SWDCLK_4") (pintype "bidirectional"))
      (node (ref "R27") (pin "1") (pinfunction "1_1") (pintype "passive"))
      (node (ref "U11") (pin "9") (pinfunction "TCK_9") (pintype "bidirectional"))
    )
    (net (code "6") (name "CONTROLLER_SWDIO") (class "Default")
      (node (ref "J5") (pin "2") (pinfunction "SWDIO_2") (pintype "bidirectional"))
      (node (ref "R26") (pin "1") (pinfunction "1_1") (pintype "passive"))
      (node (ref "U11") (pin "10") (pinfunction "PA03_10") (pintype "bidirectional"))
    )
    (net (code "7") (name "CONTROLLER_XIN") (class "Default")
      (node (ref "C1") (pin "1") (pinfunction "1_1") (pintype "bidirectional"))
      (node (ref "U11") (pin "1") (pinfunction "PA00_1") (pintype "bidirectional"))
      (node (ref "X2") (pin "3") (pinfunction "2_3") (pintype "bidirectional"))
    )
    (net (code "8") (name "CONTROLLER_XOUT") (class "Default")
      (node (ref "C2") (pin "1") (pinfunction "1_1") (pintype "bidirectional"))
      (node (ref "U11") (pin "2") (pinfunction "PA01_2") (pintype "bidirectional"))
      (node (ref "X2") (pin "1") (pinfunction "1_1") (pintype "bidirectional"))
    )
    (net (code "9") (name "GND") (class "Default")
      (node (ref "C1") (pin "2") (pinfunction "2_2") (pintype "bidirectional"))
      (node (ref "C10") (pin "1") (pinfunction "1_1") (pintype "bidirectional"))
      (node (ref "C11") (pin "2") (pinfunction "2_2") (pintype "bidirectional"))
      (node (ref "C12") (pin "2") (pinfunction "2_2") (pintype "bidirectional"))
      (node (ref "C13") (pin "2") (pinfunction "2_2") (pintype "bidirectional"))
      (node (ref "C14") (pin "2") (pinfunction "2_2") (pintype "bidirectional"))
      (node (ref "C15") (pin "2") (pinfunction "2_2") (pintype "bidirectional"))
      (node (ref "C16") (pin "2") (pinfunction "2_2") (pintype "bidirectional"))
      (node (ref "C17") (pin "2") (pinfunction "2_2") (pintype "bidirectional"))
      (node (ref "C18") (pin "2") (pinfunction "2_2") (pintype "bidirectional"))
      (node (ref "C19") (pin "2") (pinfunction "2_2") (pintype "bidirectional"))
      (node (ref "C2") (pin "2") (pinfunction "2_2") (pintype "bidirectional"))
      (node (ref "C20") (pin "2") (pinfunction "2_2") (pintype "bidirectional"))
      (node (ref "C21") (pin "2") (pinfunction "2_2") (pintype "bidirectional"))
      (node (ref "C22") (pin "2") (pinfunction "2_2") (pintype "bidirectional"))
      (node (ref "C23") (pin "2") (pinfunction "2_2") (pintype "bidirectional"))
      (node (ref "C24") (pin "2") (pinfunction "2_2") (pintype "bidirectional"))
      (node (ref "C25") (pin "1") (pinfunction "1_1") (pintype "bidirectional"))
      (node (ref "C26") (pin "1") (pinfunction "1_1") (pintype "bidirectional"))
      (node (ref "C27") (pin "2") (pinfunction "2_2") (pintype "bidirectional"))
      (node (ref "C4") (pin "2") (pinfunction "2_2") (pintype "bidirectional"))
      (node (ref "C5") (pin "2") (pinfunction "2_2") (pintype "bidirectional"))
      (node (ref "C6") (pin "2") (pinfunction "2_2") (pintype "bidirectional"))
      (node (ref "C7") (pin "2") (pinfunction "2_2") (pintype "bidirectional"))
      (node (ref "C8") (pin "2") (pinfunction "2_2") (pintype "bidirectional"))
      (node (ref "C9") (pin "1") (pinfunction "1_1") (pintype "bidirectional"))
      (node (ref "D1") (pin "ANODE") (pinfunction "ANODE_ANODE") (pintype "bidirectional"))
      (node (ref "D2") (pin "ANODE") (pinfunction "ANODE_ANODE") (pintype "bidirectional"))
      (node (ref "D3") (pin "ANODE") (pinfunction "ANODE_ANODE") (pintype "bidirectional"))
      (node (ref "D4") (pin "ANODE") (pinfunction "ANODE_ANODE") (pintype "bidirectional"))
      (node (ref "J1") (pin "1") (pinfunction "GND_1") (pintype "bidirectional"))
      (node (ref "J1") (pin "14") (pinfunction "GND_14") (pintype "bidirectional"))
      (node (ref "J2") (pin "5") (pinfunction "GND_5") (pintype "bidirectional"))
      (node (ref "J4") (pin "C5") (pinfunction "C5(GND)_C5") (pintype "bidirectional"))
      (node (ref "J5") (pin "5") (pinfunction "GND_5") (pintype "bidirectional"))
      (node (ref "P1") (pin "2") (pinfunction "P$2_2") (pintype "bidirectional"))
      (node (ref "P1") (pin "3") (pinfunction "P$2_3") (pintype "bidirectional"))
      (node (ref "P1") (pin "4") (pinfunction "P$2_4") (pintype "bidirectional"))
      (node (ref "P1") (pin "5") (pinfunction "P$2_5") (pintype "bidirectional"))
      (node (ref "P2") (pin "2") (pinfunction "P$2_2") (pintype "bidirectional"))
      (node (ref "P2") (pin "3") (pinfunction "P$2_3") (pintype "bidirectional"))
      (node (ref "P2") (pin "4") (pinfunction "P$2_4") (pintype "bidirectional"))
      (node (ref "P2") (pin "5") (pinfunction "P$2_5") (pintype "bidirectional"))
      (node (ref "Q1") (pin "S") (pinfunction "S_S") (pintype "passive"))
      (node (ref "Q2") (pin "S") (pinfunction "S_S") (pintype "passive"))
      (node (ref "Q3") (pin "S") (pinfunction "S_S") (pintype "passive"))
      (node (ref "Q4") (pin "S") (pinfunction "S_S") (pintype "passive"))
      (node (ref "R30") (pin "1") (pinfunction "1_1") (pintype "passive"))
      (node (ref "R31") (pin "1") (pinfunction "1_1") (pintype "passive"))
      (node (ref "R32") (pin "1") (pinfunction "1_1") (pintype "passive"))
      (node (ref "R35") (pin "1") (pinfunction "1_1") (pintype "passive"))
      (node (ref "R37") (pin "1") (pinfunction "1_1") (pintype "passive"))
      (node (ref "R38") (pin "1") (pinfunction "1_1") (pintype "passive"))
      (node (ref "R39") (pin "1") (pinfunction "1_1") (pintype "passive"))
      (node (ref "TP15") (pin "TP") (pinfunction "TP_TP") (pintype "input"))
      (node (ref "U1") (pin "32") (pinfunction "GND_32") (pintype "bidirectional"))
      (node (ref "U10") (pin "9") (pinfunction "GND_9") (pintype "bidirectional"))
      (node (ref "U11") (pin "23") (pinfunction "GNDANA_23") (pintype "power_in"))
      (node (ref "U11") (pin "38") (pinfunction "GND_38") (pintype "power_in"))
      (node (ref "U11") (pin "6") (pinfunction "GND_6") (pintype "power_in"))
      (node (ref "U11") (pin "64") (pinfunction "GND_64") (pintype "power_in"))
      (node (ref "U11") (pin "GND") (pinfunction "GND_GND") (pintype "power_in"))
      (node (ref "U12") (pin "P$1") (pinfunction "GND_P$1") (pintype "bidirectional"))
      (node (ref "U12") (pin "P$14") (pinfunction "GND_P$14") (pintype "bidirectional"))
      (node (ref "U12") (pin "P$20") (pinfunction "GND_P$20") (pintype "bidirectional"))
      (node (ref "U12") (pin "P$21") (pinfunction "GND_P$21") (pintype "bidirectional"))
      (node (ref "U12") (pin "P$22") (pinfunction "GND_P$22") (pintype "bidirectional"))
      (node (ref "U12") (pin "P$3") (pinfunction "GND_P$3") (pintype "bidirectional"))
      (node (ref "U12") (pin "P$30") (pinfunction "GND_P$30") (pintype "bidirectional"))
      (node (ref "U12") (pin "P$32") (pinfunction "GND_P$32") (pintype "bidirectional"))
      (node (ref "U12") (pin "P$33") (pinfunction "GND_P$33") (pintype "bidirectional"))
      (node (ref "U12") (pin "P$43") (pinfunction "GND_P$43") (pintype "bidirectional"))
      (node (ref "U12") (pin "P$5") (pinfunction "GND_P$5") (pintype "bidirectional"))
      (node (ref "U12") (pin "P$50") (pinfunction "GND_P$50") (pintype "bidirectional"))
      (node (ref "U12") (pin "P$54") (pinfunction "GND_P$54") (pintype "bidirectional"))
      (node (ref "U12") (pin "P$55") (pinfunction "GND_P$55") (pintype "bidirectional"))
      (node (ref "U12") (pin "P$57") (pinfunction "GND_P$57") (pintype "bidirectional"))
      (node (ref "U12") (pin "P$58") (pinfunction "GND_P$58") (pintype "bidirectional"))
      (node (ref "U12") (pin "P$59") (pinfunction "GND_P$59") (pintype "bidirectional"))
      (node (ref "U12") (pin "P$60") (pinfunction "GND_P$60") (pintype "bidirectional"))
      (node (ref "U12") (pin "P$61") (pinfunction "GND_P$61") (pintype "bidirectional"))
      (node (ref "U12") (pin "P$63") (pinfunction "GND_P$63") (pintype "bidirectional"))
      (node (ref "U12") (pin "P$64") (pinfunction "GND_P$64") (pintype "bidirectional"))
      (node (ref "U12") (pin "P$9") (pinfunction "DTR_P$9") (pintype "bidirectional"))
      (node (ref "U12") (pin "P65") (pinfunction "GND_P65") (pintype "bidirectional"))
      (node (ref "U12") (pin "P66") (pinfunction "GND_P66") (pintype "bidirectional"))
      (node (ref "U12") (pin "P67") (pinfunction "GND_P67") (pintype "bidirectional"))
      (node (ref "U12") (pin "P68") (pinfunction "GND_P68") (pintype "bidirectional"))
      (node (ref "U12") (pin "P69") (pinfunction "GND_P69") (pintype "bidirectional"))
      (node (ref "U12") (pin "P70") (pinfunction "GND_P70") (pintype "bidirectional"))
      (node (ref "U12") (pin "P71") (pinfunction "GND_P71") (pintype "bidirectional"))
      (node (ref "U12") (pin "P72") (pinfunction "GND_P72") (pintype "bidirectional"))
      (node (ref "U12") (pin "P73") (pinfunction "GND_P73") (pintype "bidirectional"))
      (node (ref "U12") (pin "P74") (pinfunction "GND_P74") (pintype "bidirectional"))
      (node (ref "U12") (pin "P75") (pinfunction "GND_P75") (pintype "bidirectional"))
      (node (ref "U12") (pin "P76") (pinfunction "GND_P76") (pintype "bidirectional"))
      (node (ref "U12") (pin "P77") (pinfunction "GND_P77") (pintype "bidirectional"))
      (node (ref "U12") (pin "P78") (pinfunction "GND_P78") (pintype "bidirectional"))
      (node (ref "U12") (pin "P79") (pinfunction "GND_P79") (pintype "bidirectional"))
      (node (ref "U12") (pin "P80") (pinfunction "GND_P80") (pintype "bidirectional"))
      (node (ref "U12") (pin "P81") (pinfunction "GND_P81") (pintype "bidirectional"))
      (node (ref "U12") (pin "P82") (pinfunction "GND_P82") (pintype "bidirectional"))
      (node (ref "U12") (pin "P83") (pinfunction "GND_P83") (pintype "bidirectional"))
      (node (ref "U12") (pin "P84") (pinfunction "GND_P84") (pintype "bidirectional"))
      (node (ref "U12") (pin "P85") (pinfunction "GND_P85") (pintype "bidirectional"))
      (node (ref "U12") (pin "P86") (pinfunction "GND_P86") (pintype "bidirectional"))
      (node (ref "U12") (pin "P87") (pinfunction "GND_P87") (pintype "bidirectional"))
      (node (ref "U12") (pin "P88") (pinfunction "GND_P88") (pintype "bidirectional"))
      (node (ref "U12") (pin "P89") (pinfunction "GND_P89") (pintype "bidirectional"))
      (node (ref "U12") (pin "P90") (pinfunction "GND_P90") (pintype "bidirectional"))
      (node (ref "U12") (pin "P91") (pinfunction "GND_P91") (pintype "bidirectional"))
      (node (ref "U12") (pin "P92") (pinfunction "GND_P92") (pintype "bidirectional"))
      (node (ref "U12") (pin "P93") (pinfunction "GND_P93") (pintype "bidirectional"))
      (node (ref "U12") (pin "P94") (pinfunction "GND_P94") (pintype "bidirectional"))
      (node (ref "U12") (pin "P95") (pinfunction "GND_P95") (pintype "bidirectional"))
      (node (ref "U12") (pin "P96") (pinfunction "GND_P96") (pintype "bidirectional"))
      (node (ref "U2") (pin "15") (pinfunction "PGND_15") (pintype "bidirectional"))
      (node (ref "U2") (pin "16") (pinfunction "PGND_16") (pintype "bidirectional"))
      (node (ref "U2") (pin "6") (pinfunction "AGND_6") (pintype "bidirectional"))
      (node (ref "U2") (pin "7") (pinfunction "FSW_7") (pintype "bidirectional"))
      (node (ref "U2") (pin "8") (pinfunction "DEF_8") (pintype "bidirectional"))
      (node (ref "U2") (pin "GND") (pinfunction "PGND_GND") (pintype "bidirectional"))
      (node (ref "U4") (pin "2") (pinfunction "GND_2") (pintype "open_collector"))
      (node (ref "U5") (pin "2") (pinfunction "GND_2") (pintype "open_collector"))
      (node (ref "U6") (pin "1") (pinfunction "GND_1") (pintype "bidirectional"))
      (node (ref "U6") (pin "11") (pinfunction "GND_11") (pintype "bidirectional"))
      (node (ref "U6") (pin "16") (pinfunction "GND_16") (pintype "bidirectional"))
      (node (ref "U6") (pin "22") (pinfunction "GND_22") (pintype "bidirectional"))
      (node (ref "U6") (pin "27") (pinfunction "GND_27") (pintype "bidirectional"))
      (node (ref "U6") (pin "30") (pinfunction "GND_30") (pintype "bidirectional"))
      (node (ref "U6") (pin "32") (pinfunction "GND_32") (pintype "bidirectional"))
      (node (ref "U6") (pin "6") (pinfunction "GND_6") (pintype "bidirectional"))
      (node (ref "U7") (pin "1") (pinfunction "A0_1") (pintype "bidirectional"))
      (node (ref "U7") (pin "10") (pinfunction "GND_10") (pintype "bidirectional"))
      (node (ref "U7") (pin "2") (pinfunction "A1_2") (pintype "bidirectional"))
      (node (ref "U7") (pin "3") (pinfunction "A2_3") (pintype "bidirectional"))
      (node (ref "U8") (pin "15") (pinfunction "PGND_15") (pintype "bidirectional"))
      (node (ref "U8") (pin "16") (pinfunction "PGND_16") (pintype "bidirectional"))
      (node (ref "U8") (pin "6") (pinfunction "AGND_6") (pintype "bidirectional"))
      (node (ref "U8") (pin "7") (pinfunction "FSW_7") (pintype "bidirectional"))
      (node (ref "U8") (pin "8") (pinfunction "DEF_8") (pintype "bidirectional"))
      (node (ref "U8") (pin "GND") (pinfunction "PGND_GND") (pintype "bidirectional"))
      (node (ref "U9") (pin "2") (pinfunction "GND_2") (pintype "open_collector"))
      (node (ref "X2") (pin "2") (pinfunction "GND_2") (pintype "bidirectional"))
      (node (ref "X2") (pin "4") (pinfunction "GND_4") (pintype "bidirectional"))
    )
    (net (code "10") (name "GSM_3V8") (class "Default")
      (node (ref "Q5") (pin "2") (pinfunction "S_2") (pintype "passive"))
      (node (ref "R33") (pin "2") (pinfunction "2_2") (pintype "passive"))
      (node (ref "R5") (pin "1") (pinfunction "1_1") (pintype "passive"))
      (node (ref "R8") (pin "2") (pinfunction "2_2") (pintype "passive"))
      (node (ref "U9") (pin "6") (pinfunction "SENSE-_6") (pintype "open_collector"))
    )
    (net (code "11") (name "GSM_AUX_RX") (class "Default")
      (node (ref "U10") (pin "10") (pinfunction "B6_10") (pintype "bidirectional"))
      (node (ref "U11") (pin "43") (pinfunction "PA16_43") (pintype "bidirectional"))
    )
    (net (code "12") (name "GSM_AUX_TX") (class "Default")
      (node (ref "U10") (pin "11") (pinfunction "B5_11") (pintype "bidirectional"))
      (node (ref "U11") (pin "42") (pinfunction "PA15_42") (pintype "bidirectional"))
    )
    (net (code "13") (name "GSM_CTS") (class "Default")
      (node (ref "TP11") (pin "TP") (pinfunction "TP_TP") (pintype "input"))
      (node (ref "U10") (pin "14") (pinfunction "B2_14") (pintype "bidirectional"))
      (node (ref "U11") (pin "29") (pinfunction "PA09_29") (pintype "bidirectional"))
    )
    (net (code "14") (name "GSM_GAUGE_ALERT") (class "Default")
      (node (ref "R21") (pin "1") (pinfunction "1_1") (pintype "passive"))
      (node (ref "U7") (pin "11") (pinfunction "~{INT2}_11") (pintype "bidirectional"))
      (node (ref "U9") (pin "5") (pinfunction "~{ALERT}_5") (pintype "open_collector"))
    )
    (net (code "15") (name "GSM_GAUGE_SCL") (class "Default")
      (node (ref "R22") (pin "1") (pinfunction "1_1") (pintype "passive"))
      (node (ref "U7") (pin "13") (pinfunction "SC2_13") (pintype "bidirectional"))
      (node (ref "U9") (pin "3") (pinfunction "SCL_3") (pintype "open_collector"))
    )
    (net (code "16") (name "GSM_GAUGE_SDA") (class "Default")
      (node (ref "R23") (pin "1") (pinfunction "1_1") (pintype "passive"))
      (node (ref "U7") (pin "12") (pinfunction "SD2_12") (pintype "bidirectional"))
      (node (ref "U9") (pin "4") (pinfunction "SDA_4") (pintype "open_collector"))
    )
    (net (code "17") (name "GSM_GPIO2") (class "Default")
      (node (ref "TP10") (pin "TP") (pinfunction "TP_TP") (pintype "input"))
      (node (ref "U11") (pin "30") (pinfunction "PA10_30") (pintype "bidirectional"))
      (node (ref "U12") (pin "P$23") (pinfunction "GPIO2_P$23") (pintype "bidirectional"))
    )
    (net (code "18") (name "GSM_LED") (class "Default")
      (node (ref "Q1") (pin "G") (pinfunction "G_G") (pintype "passive"))
      (node (ref "R31") (pin "2") (pinfunction "2_2") (pintype "passive"))
      (node (ref "U12") (pin "P$16") (pinfunction "GPIO1_P$16") (pintype "bidirectional"))
    )
    (net (code "19") (name "GSM_POWER") (class "Default")
      (node (ref "Q3") (pin "G") (pinfunction "G_G") (pintype "passive"))
      (node (ref "TP6") (pin "TP") (pinfunction "TP_TP") (pintype "input"))
      (node (ref "U11") (pin "41") (pinfunction "PA14_41") (pintype "bidirectional"))
    )
    (net (code "20") (name "GSM_POWER_GATE") (class "Default")
      (node (ref "Q5") (pin "1") (pinfunction "G_1") (pintype "passive"))
      (node (ref "R32") (pin "2") (pinfunction "2_2") (pintype "passive"))
      (node (ref "R33") (pin "1") (pinfunction "1_1") (pintype "passive"))
      (node (ref "U11") (pin "22") (pinfunction "PA07_22") (pintype "bidirectional"))
    )
    (net (code "21") (name "GSM_RTS") (class "Default")
      (node (ref "TP12") (pin "TP") (pinfunction "TP_TP") (pintype "input"))
      (node (ref "U10") (pin "16") (pinfunction "B1_16") (pintype "bidirectional"))
      (node (ref "U11") (pin "26") (pinfunction "PA08_26") (pintype "bidirectional"))
    )
    (net (code "22") (name "GSM_RX") (class "Default")
      (node (ref "TP8") (pin "TP") (pinfunction "TP_TP") (pintype "input"))
      (node (ref "U10") (pin "12") (pinfunction "B4_12") (pintype "bidirectional"))
      (node (ref "U11") (pin "32") (pinfunction "PA12_32") (pintype "bidirectional"))
    )
    (net (code "23") (name "GSM_TX") (class "Default")
      (node (ref "TP9") (pin "TP") (pinfunction "TP_TP") (pintype "input"))
      (node (ref "U10") (pin "13") (pinfunction "B3_13") (pintype "bidirectional"))
      (node (ref "U11") (pin "31") (pinfunction "PA11_31") (pintype "bidirectional"))
    )
    (net (code "24") (name "IM880_3V3") (class "Default")
      (node (ref "Q7") (pin "2") (pinfunction "S_2") (pintype "passive"))
      (node (ref "R36") (pin "2") (pinfunction "2_2") (pintype "passive"))
      (node (ref "R6") (pin "1") (pinfunction "1_1") (pintype "passive"))
      (node (ref "R9") (pin "2") (pinfunction "2_2") (pintype "passive"))
      (node (ref "U4") (pin "6") (pinfunction "SENSE-_6") (pintype "open_collector"))
    )
    (net (code "25") (name "IM880_BOOT") (class "Default")
      (node (ref "U11") (pin "49") (pinfunction "PA18_49") (pintype "bidirectional"))
      (node (ref "U6") (pin "26") (pinfunction "BOOT_26") (pintype "bidirectional"))
    )
    (net (code "26") (name "IM880_CS") (class "Default")
      (node (ref "U11") (pin "60") (pinfunction "PA24_60") (pintype "bidirectional"))
      (node (ref "U6") (pin "15") (pinfunction "P10_15") (pintype "bidirectional"))
    )
    (net (code "27") (name "IM880_GATED") (class "Default")
      (node (ref "C21") (pin "1") (pinfunction "1_1") (pintype "bidirectional"))
      (node (ref "J2") (pin "1") (pinfunction "VCC_1") (pintype "bidirectional"))
      (node (ref "Q7") (pin "3") (pinfunction "D_3") (pintype "passive"))
      (node (ref "U6") (pin "17") (pinfunction "VDD_17") (pintype "bidirectional"))
    )
    (net (code "28") (name "IM880_GAUGE_ALERT") (class "Default")
      (node (ref "R18") (pin "1") (pinfunction "1_1") (pintype "passive"))
      (node (ref "U4") (pin "5") (pinfunction "~{ALERT}_5") (pintype "open_collector"))
      (node (ref "U7") (pin "7") (pinfunction "~{INT1}_7") (pintype "bidirectional"))
    )
    (net (code "29") (name "IM880_GAUGE_SCL") (class "Default")
      (node (ref "R19") (pin "1") (pinfunction "1_1") (pintype "passive"))
      (node (ref "U4") (pin "3") (pinfunction "SCL_3") (pintype "open_collector"))
      (node (ref "U7") (pin "9") (pinfunction "SC1_9") (pintype "bidirectional"))
    )
    (net (code "30") (name "IM880_GAUGE_SDA") (class "Default")
      (node (ref "R20") (pin "1") (pinfunction "1_1") (pintype "passive"))
      (node (ref "U4") (pin "4") (pinfunction "SDA_4") (pintype "open_collector"))
      (node (ref "U7") (pin "8") (pinfunction "SD1_8") (pintype "bidirectional"))
    )
    (net (code "31") (name "IM880_INT1") (class "Default")
      (node (ref "U11") (pin "15") (pinfunction "PA04_15") (pintype "bidirectional"))
      (node (ref "U6") (pin "8") (pinfunction "P5_8") (pintype "bidirectional"))
    )
    (net (code "32") (name "IM880_INT2") (class "Default")
      (node (ref "U11") (pin "16") (pinfunction "PA05_16") (pintype "bidirectional"))
      (node (ref "U6") (pin "9") (pinfunction "P6_9") (pintype "bidirectional"))
    )
    (net (code "33") (name "IM880_POWER_GATE") (class "Default")
      (node (ref "Q7") (pin "1") (pinfunction "G_1") (pintype "passive"))
      (node (ref "R36") (pin "1") (pinfunction "1_1") (pintype "passive"))
      (node (ref "R37") (pin "2") (pinfunction "2_2") (pintype "passive"))
      (node (ref "U11") (pin "21") (pinfunction "PA06_21") (pintype "bidirectional"))
    )
    (net (code "34") (name "IM880_RX") (class "Default")
      (node (ref "U11") (pin "51") (pinfunction "PA20_51") (pintype "bidirectional"))
      (node (ref "U6") (pin "18") (pinfunction "RXD_18") (pintype "bidirectional"))
    )
    (net (code "35") (name "IM880_SWCLK") (class "Default")
      (node (ref "J2") (pin "4") (pinfunction "SWDCLK_4") (pintype "bidirectional"))
      (node (ref "U6") (pin "2") (pinfunction "P1/SWCLK_2") (pintype "bidirectional"))
    )
    (net (code "36") (name "IM880_SWDIO") (class "Default")
      (node (ref "J2") (pin "2") (pinfunction "SWDIO_2") (pintype "bidirectional"))
      (node (ref "U6") (pin "3") (pinfunction "P2/SWDIO_3") (pintype "bidirectional"))
    )
    (net (code "37") (name "IM880_TX") (class "Default")
      (node (ref "U11") (pin "50") (pinfunction "PA19_50") (pintype "bidirectional"))
      (node (ref "U6") (pin "19") (pinfunction "TXD_19") (pintype "bidirectional"))
    )
    (net (code "38") (name "MISO") (class "Default")
      (node (ref "U1") (pin "14") (pinfunction "SPI_MISO/P29_14") (pintype "bidirectional"))
      (node (ref "U11") (pin "55") (pinfunction "PA21_55") (pintype "bidirectional"))
      (node (ref "U6") (pin "12") (pinfunction "P7_12") (pintype "bidirectional"))
    )
    (net (code "39") (name "MOD_IN") (class "Default")
      (node (ref "J1") (pin "10") (pinfunction "MOD_IN_10") (pintype "bidirectional"))
      (node (ref "TP3") (pin "TP") (pinfunction "TP_TP") (pintype "input"))
      (node (ref "U11") (pin "20") (pinfunction "PB05_20") (pintype "bidirectional"))
    )
    (net (code "40") (name "MOD_OUT") (class "Default")
      (node (ref "J1") (pin "8") (pinfunction "MOD_OUT_8") (pintype "bidirectional"))
      (node (ref "TP1") (pin "TP") (pinfunction "TP_TP") (pintype "input"))
      (node (ref "U11") (pin "14") (pinfunction "PB03_14") (pintype "bidirectional"))
    )
    (net (code "41") (name "MOSI") (class "Default")
      (node (ref "U1") (pin "15") (pinfunction "SPI_MOSI/P30_15") (pintype "bidirectional"))
      (node (ref "U11") (pin "56") (pinfunction "PA22_56") (pintype "bidirectional"))
      (node (ref "U6") (pin "13") (pinfunction "P8_13") (pintype "bidirectional"))
    )
    (net (code "42") (name "NUCLEUM_3V3") (class "Default")
      (node (ref "Q6") (pin "2") (pinfunction "S_2") (pintype "passive"))
      (node (ref "R34") (pin "2") (pinfunction "2_2") (pintype "passive"))
      (node (ref "R7") (pin "1") (pinfunction "1_1") (pintype "passive"))
      (node (ref "U5") (pin "6") (pinfunction "SENSE-_6") (pintype "open_collector"))
    )
    (net (code "43") (name "NUCLEUM_BOOT") (class "Default")
      (node (ref "U1") (pin "24") (pinfunction "BTLDR_CTRL/P13_24") (pintype "bidirectional"))
      (node (ref "U11") (pin "45") (pinfunction "PB08_45") (pintype "bidirectional"))
    )
    (net (code "44") (name "NUCLEUM_CS") (class "Default")
      (node (ref "U1") (pin "19") (pinfunction "P08_19") (pintype "bidirectional"))
      (node (ref "U11") (pin "54") (pinfunction "PB13_54") (pintype "bidirectional"))
    )
    (net (code "45") (name "NUCLEUM_GAUGE_ALERT") (class "Default")
      (node (ref "R15") (pin "1") (pinfunction "1_1") (pintype "passive"))
      (node (ref "U5") (pin "5") (pinfunction "~{ALERT}_5") (pintype "open_collector"))
      (node (ref "U7") (pin "4") (pinfunction "~{INT0}_4") (pintype "bidirectional"))
    )
    (net (code "46") (name "NUCLEUM_GAUGE_SCL") (class "Default")
      (node (ref "R16") (pin "1") (pinfunction "1_1") (pintype "passive"))
      (node (ref "U5") (pin "3") (pinfunction "SCL_3") (pintype "open_collector"))
      (node (ref "U7") (pin "6") (pinfunction "SC0_6") (pintype "bidirectional"))
    )
    (net (code "47") (name "NUCLEUM_GAUGE_SDA") (class "Default")
      (node (ref "R17") (pin "1") (pinfunction "1_1") (pintype "passive"))
      (node (ref "U5") (pin "4") (pinfunction "SDA_4") (pintype "open_collector"))
      (node (ref "U7") (pin "5") (pinfunction "SD0_5") (pintype "bidirectional"))
    )
    (net (code "48") (name "NUCLEUM_INT1{slash}RTS") (class "Default")
      (node (ref "U1") (pin "20") (pinfunction "P09_20") (pintype "bidirectional"))
      (node (ref "U11") (pin "27") (pinfunction "PB06_27") (pintype "bidirectional"))
    )
    (net (code "49") (name "NUCLEUM_INT2{slash}CTS") (class "Default")
      (node (ref "U1") (pin "21") (pinfunction "P10_21") (pintype "bidirectional"))
      (node (ref "U11") (pin "28") (pinfunction "PB07_28") (pintype "bidirectional"))
    )
    (net (code "50") (name "NUCLEUM_POWER_GATE") (class "Default")
      (node (ref "Q6") (pin "1") (pinfunction "G_1") (pintype "passive"))
      (node (ref "R34") (pin "1") (pinfunction "1_1") (pintype "passive"))
      (node (ref "R35") (pin "2") (pinfunction "2_2") (pintype "passive"))
      (node (ref "U11") (pin "48") (pinfunction "PB11_48") (pintype "bidirectional"))
    )
    (net (code "51") (name "NUCLEUM_RX") (class "Default")
      (node (ref "U1") (pin "22") (pinfunction "BTLDR_RX/P11_22") (pintype "bidirectional"))
      (node (ref "U11") (pin "47") (pinfunction "PB10_47") (pintype "bidirectional"))
    )
    (net (code "52") (name "NUCLEUM_TX") (class "Default")
      (node (ref "U1") (pin "23") (pinfunction "BTLDR_TX/P12_23") (pintype "bidirectional"))
      (node (ref "U11") (pin "46") (pinfunction "PB09_46") (pintype "bidirectional"))
    )
    (net (code "53") (name "Net-(FB4-P$1)") (class "Default")
      (node (ref "C15") (pin "1") (pinfunction "1_1") (pintype "bidirectional"))
      (node (ref "FB4") (pin "1") (pinfunction "P$1_1") (pintype "bidirectional"))
      (node (ref "U11") (pin "25") (pinfunction "VDDANA_25") (pintype "power_in"))
    )
    (net (code "54") (name "Net-(J4-C1(VCC))") (class "Default")
      (node (ref "C7") (pin "1") (pinfunction "1_1") (pintype "bidirectional"))
      (node (ref "D1") (pin "CATHODE") (pinfunction "CATHODE_CATHODE") (pintype "bidirectional"))
      (node (ref "J4") (pin "C1") (pinfunction "C1(VCC)_C1") (pintype "bidirectional"))
      (node (ref "U12") (pin "P$41") (pinfunction "VSIM_P$41") (pintype "bidirectional"))
    )
    (net (code "55") (name "Net-(J4-C2(RST))") (class "Default")
      (node (ref "C6") (pin "1") (pinfunction "1_1") (pintype "bidirectional"))
      (node (ref "D3") (pin "CATHODE") (pinfunction "CATHODE_CATHODE") (pintype "bidirectional"))
      (node (ref "J4") (pin "C2") (pinfunction "C2(RST)_C2") (pintype "bidirectional"))
      (node (ref "U12") (pin "P$40") (pinfunction "SIM_RST_P$40") (pintype "bidirectional"))
    )
    (net (code "56") (name "Net-(J4-C3(CLK))") (class "Default")
      (node (ref "C4") (pin "1") (pinfunction "1_1") (pintype "bidirectional"))
      (node (ref "D4") (pin "CATHODE") (pinfunction "CATHODE_CATHODE") (pintype "bidirectional"))
      (node (ref "J4") (pin "C3") (pinfunction "C3(CLK)_C3") (pintype "bidirectional"))
      (node (ref "U12") (pin "P$38") (pinfunction "SIM_CLK_P$38") (pintype "bidirectional"))
    )
    (net (code "57") (name "Net-(J4-C7(IO))") (class "Default")
      (node (ref "C5") (pin "1") (pinfunction "1_1") (pintype "bidirectional"))
      (node (ref "D2") (pin "CATHODE") (pinfunction "CATHODE_CATHODE") (pintype "bidirectional"))
      (node (ref "J4") (pin "C7") (pinfunction "C7(IO)_C7") (pintype "bidirectional"))
      (node (ref "U12") (pin "P$39") (pinfunction "SIM_IO_P$39") (pintype "bidirectional"))
    )
    (net (code "58") (name "Net-(L1-1)") (class "Default")
      (node (ref "L1") (pin "P$1") (pinfunction "1_P$1") (pintype "bidirectional"))
      (node (ref "U2") (pin "1") (pinfunction "SW_1") (pintype "bidirectional"))
      (node (ref "U2") (pin "2") (pinfunction "SW_2") (pintype "bidirectional"))
      (node (ref "U2") (pin "3") (pinfunction "SW_3") (pintype "bidirectional"))
    )
    (net (code "59") (name "Net-(L2-1)") (class "Default")
      (node (ref "L2") (pin "P$1") (pinfunction "1_P$1") (pintype "bidirectional"))
      (node (ref "U8") (pin "1") (pinfunction "SW_1") (pintype "bidirectional"))
      (node (ref "U8") (pin "2") (pinfunction "SW_2") (pintype "bidirectional"))
      (node (ref "U8") (pin "3") (pinfunction "SW_3") (pintype "bidirectional"))
    )
    (net (code "60") (name "Net-(L3-1)") (class "Default")
      (node (ref "C19") (pin "1") (pinfunction "1_1") (pintype "bidirectional"))
      (node (ref "C22") (pin "1") (pinfunction "1_1") (pintype "bidirectional"))
      (node (ref "L3") (pin "P$1") (pinfunction "1_P$1") (pintype "bidirectional"))
      (node (ref "U11") (pin "7") (pinfunction "VDDOUT_7") (pintype "power_in"))
    )
    (net (code "61") (name "Net-(L3-2)") (class "Default")
      (node (ref "L3") (pin "P$2") (pinfunction "2_P$2") (pintype "bidirectional"))
      (node (ref "U11") (pin "5") (pinfunction "VDDCORE_5") (pintype "power_in"))
    )
    (net (code "62") (name "Net-(LED1-ANODE)") (class "Default")
      (node (ref "LED1") (pin "A") (pinfunction "ANODE_A") (pintype "bidirectional"))
      (node (ref "R8") (pin "1") (pinfunction "1_1") (pintype "passive"))
    )
    (net (code "63") (name "Net-(LED1-CATHODE)") (class "Default")
      (node (ref "LED1") (pin "C") (pinfunction "CATHODE_C") (pintype "bidirectional"))
      (node (ref "Q1") (pin "D") (pinfunction "D_D") (pintype "passive"))
    )
    (net (code "64") (name "Net-(LED2-ANODE)") (class "Default")
      (node (ref "LED2") (pin "A") (pinfunction "ANODE_A") (pintype "bidirectional"))
      (node (ref "R9") (pin "1") (pinfunction "1_1") (pintype "passive"))
    )
    (net (code "65") (name "Net-(LED2-CATHODE)") (class "Default")
      (node (ref "LED2") (pin "C") (pinfunction "CATHODE_C") (pintype "bidirectional"))
      (node (ref "Q4") (pin "D") (pinfunction "D_D") (pintype "passive"))
    )
    (net (code "66") (name "Net-(P1-ANT)") (class "Default")
      (node (ref "C3") (pin "2") (pinfunction "2_2") (pintype "bidirectional"))
      (node (ref "P1") (pin "1") (pinfunction "ANT_1") (pintype "bidirectional"))
    )
    (net (code "67") (name "Net-(P2-ANT)") (class "Default")
      (node (ref "P2") (pin "1") (pinfunction "ANT_1") (pintype "bidirectional"))
      (node (ref "U6") (pin "31") (pinfunction "RF_31") (pintype "bidirectional"))
    )
    (net (code "68") (name "Net-(Q5-D)") (class "Default")
      (node (ref "C11") (pin "1") (pinfunction "1_1") (pintype "bidirectional"))
      (node (ref "C14") (pin "1") (pinfunction "1_1") (pintype "bidirectional"))
      (node (ref "C27") (pin "1") (pinfunction "1_1") (pintype "bidirectional"))
      (node (ref "C8") (pin "1") (pinfunction "1_1") (pintype "bidirectional"))
      (node (ref "Q5") (pin "3") (pinfunction "D_3") (pintype "passive"))
      (node (ref "U12") (pin "P$51") (pinfunction "VCC_P$51") (pintype "bidirectional"))
      (node (ref "U12") (pin "P$52") (pinfunction "VCC_P$52") (pintype "bidirectional"))
      (node (ref "U12") (pin "P$53") (pinfunction "VCC_P$53") (pintype "bidirectional"))
    )
    (net (code "69") (name "Net-(Q6-D)") (class "Default")
      (node (ref "Q6") (pin "3") (pinfunction "D_3") (pintype "passive"))
      (node (ref "U1") (pin "1") (pinfunction "VCC_1") (pintype "bidirectional"))
    )
    (net (code "70") (name "Net-(U2-FB)") (class "Default")
      (node (ref "R39") (pin "2") (pinfunction "2_2") (pintype "passive"))
      (node (ref "R40") (pin "1") (pinfunction "1_1") (pintype "passive"))
      (node (ref "U2") (pin "5") (pinfunction "FB_5") (pintype "bidirectional"))
    )
    (net (code "71") (name "Net-(U2-PG)") (class "Default")
      (node (ref "R28") (pin "1") (pinfunction "1_1") (pintype "passive"))
      (node (ref "U2") (pin "4") (pinfunction "PG_4") (pintype "bidirectional"))
    )
    (net (code "72") (name "Net-(U2-SS{slash}TR)") (class "Default")
      (node (ref "C9") (pin "2") (pinfunction "2_2") (pintype "bidirectional"))
      (node (ref "U2") (pin "9") (pinfunction "SS/TR_9") (pintype "bidirectional"))
    )
    (net (code "73") (name "Net-(U6-P3)") (class "Default")
      (node (ref "Q4") (pin "G") (pinfunction "G_G") (pintype "passive"))
      (node (ref "R30") (pin "2") (pinfunction "2_2") (pintype "passive"))
      (node (ref "U6") (pin "4") (pinfunction "P3_4") (pintype "bidirectional"))
    )
    (net (code "74") (name "Net-(U6-P12)") (class "Default")
      (node (ref "R2") (pin "1") (pinfunction "1_1") (pintype "passive"))
      (node (ref "U6") (pin "21") (pinfunction "P12_21") (pintype "bidirectional"))
    )
    (net (code "75") (name "Net-(U6-P13)") (class "Default")
      (node (ref "R1") (pin "1") (pinfunction "1_1") (pintype "passive"))
      (node (ref "U6") (pin "23") (pinfunction "P13_23") (pintype "bidirectional"))
    )
    (net (code "76") (name "Net-(U7-~{INT3})") (class "Default")
      (node (ref "R24") (pin "2") (pinfunction "2_2") (pintype "passive"))
      (node (ref "U7") (pin "14") (pinfunction "~{INT3}_14") (pintype "bidirectional"))
    )
    (net (code "77") (name "Net-(U8-FB)") (class "Default")
      (node (ref "R38") (pin "2") (pinfunction "2_2") (pintype "passive"))
      (node (ref "R41") (pin "1") (pinfunction "1_1") (pintype "passive"))
      (node (ref "U8") (pin "5") (pinfunction "FB_5") (pintype "bidirectional"))
    )
    (net (code "78") (name "Net-(U8-PG)") (class "Default")
      (node (ref "R29") (pin "1") (pinfunction "1_1") (pintype "passive"))
      (node (ref "U8") (pin "4") (pinfunction "PG_4") (pintype "bidirectional"))
    )
    (net (code "79") (name "Net-(U8-SS{slash}TR)") (class "Default")
      (node (ref "C10") (pin "2") (pinfunction "2_2") (pintype "bidirectional"))
      (node (ref "U8") (pin "9") (pinfunction "SS/TR_9") (pintype "bidirectional"))
    )
    (net (code "80") (name "Net-(U10-A1)") (class "Default")
      (node (ref "U10") (pin "1") (pinfunction "A1_1") (pintype "bidirectional"))
      (node (ref "U12") (pin "P$10") (pinfunction "RTS_P$10") (pintype "bidirectional"))
    )
    (net (code "81") (name "Net-(U10-A2)") (class "Default")
      (node (ref "U10") (pin "3") (pinfunction "A2_3") (pintype "bidirectional"))
      (node (ref "U12") (pin "P$11") (pinfunction "CTS_P$11") (pintype "bidirectional"))
    )
    (net (code "82") (name "Net-(U10-A3)") (class "Default")
      (node (ref "U10") (pin "4") (pinfunction "A3_4") (pintype "bidirectional"))
      (node (ref "U12") (pin "P$12") (pinfunction "TXD_P$12") (pintype "bidirectional"))
    )
    (net (code "83") (name "Net-(U10-A4)") (class "Default")
      (node (ref "U10") (pin "5") (pinfunction "A4_5") (pintype "bidirectional"))
      (node (ref "U12") (pin "P$13") (pinfunction "RXD_P$13") (pintype "bidirectional"))
    )
    (net (code "84") (name "Net-(U10-A5)") (class "Default")
      (node (ref "JP1") (pin "2") (pinfunction "2_2") (pintype "passive"))
      (node (ref "U10") (pin "6") (pinfunction "A5_6") (pintype "bidirectional"))
      (node (ref "U12") (pin "P$29") (pinfunction "TXD_AUX_P$29") (pintype "bidirectional"))
    )
    (net (code "85") (name "Net-(U10-A6)") (class "Default")
      (node (ref "JP1") (pin "1") (pinfunction "1_1") (pintype "passive"))
      (node (ref "U10") (pin "7") (pinfunction "A6_7") (pintype "bidirectional"))
      (node (ref "U12") (pin "P$28") (pinfunction "RXD_AUX_P$28") (pintype "bidirectional"))
    )
    (net (code "86") (name "Net-(U10-OE)") (class "Default")
      (node (ref "R10") (pin "1") (pinfunction "1_1") (pintype "passive"))
      (node (ref "U10") (pin "8") (pinfunction "OE_8") (pintype "bidirectional"))
    )
    (net (code "87") (name "Net-(U11-BIASH)") (class "Default")
      (node (ref "U11") (pin "36") (pinfunction "BIASH_36") (pintype "bidirectional"))
      (node (ref "U11") (pin "37") (pinfunction "BIASL_37") (pintype "bidirectional"))
    )
    (net (code "88") (name "Net-(U11-CAPH)") (class "Default")
      (node (ref "U11") (pin "33") (pinfunction "CAPH_33") (pintype "bidirectional"))
      (node (ref "U11") (pin "34") (pinfunction "CAPL_34") (pintype "bidirectional"))
    )
    (net (code "89") (name "Net-(U11-PA02)") (class "Default")
      (node (ref "R11") (pin "1") (pinfunction "1_1") (pintype "passive"))
      (node (ref "U11") (pin "3") (pinfunction "PA02_3") (pintype "bidirectional"))
    )
    (net (code "90") (name "Net-(U11-PB00)") (class "Default")
      (node (ref "R3") (pin "1") (pinfunction "1_1") (pintype "passive"))
      (node (ref "U11") (pin "11") (pinfunction "PB00_11") (pintype "bidirectional"))
    )
    (net (code "91") (name "Net-(U11-PB01)") (class "Default")
      (node (ref "R4") (pin "1") (pinfunction "1_1") (pintype "passive"))
      (node (ref "U11") (pin "12") (pinfunction "PB01_12") (pintype "bidirectional"))
    )
    (net (code "92") (name "Net-(U11-PB12)") (class "Default")
      (node (ref "R14") (pin "2") (pinfunction "2_2") (pintype "passive"))
      (node (ref "TP13") (pin "TP") (pinfunction "TP_TP") (pintype "input"))
      (node (ref "U11") (pin "53") (pinfunction "PB12_53") (pintype "bidirectional"))
      (node (ref "U7") (pin "17") (pinfunction "~{INT}_17") (pintype "bidirectional"))
    )
    (net (code "93") (name "Net-(U11-PB14)") (class "Default")
      (node (ref "R12") (pin "2") (pinfunction "2_2") (pintype "passive"))
      (node (ref "TP4") (pin "TP") (pinfunction "TP_TP") (pintype "input"))
      (node (ref "U11") (pin "57") (pinfunction "PB14_57") (pintype "bidirectional"))
      (node (ref "U7") (pin "19") (pinfunction "SDA_19") (pintype "bidirectional"))
    )
    (net (code "94") (name "Net-(U11-PB15)") (class "Default")
      (node (ref "R13") (pin "2") (pinfunction "2_2") (pintype "passive"))
      (node (ref "TP5") (pin "TP") (pinfunction "TP_TP") (pintype "input"))
      (node (ref "U11") (pin "58") (pinfunction "PB15_58") (pintype "bidirectional"))
      (node (ref "U7") (pin "18") (pinfunction "SCL_18") (pintype "bidirectional"))
    )
    (net (code "95") (name "Net-(U12-ANT)") (class "Default")
      (node (ref "C3") (pin "1") (pinfunction "1_1") (pintype "bidirectional"))
      (node (ref "U12") (pin "P$56") (pinfunction "ANT_P$56") (pintype "bidirectional"))
    )
    (net (code "96") (name "Net-(U12-PWR_ON)") (class "Default")
      (node (ref "Q3") (pin "D") (pinfunction "D_D") (pintype "passive"))
      (node (ref "R25") (pin "1") (pinfunction "1_1") (pintype "passive"))
      (node (ref "U12") (pin "P$15") (pinfunction "PWR_ON_P$15") (pintype "bidirectional"))
    )
    (net (code "97") (name "Net-(U12-RESET_N)") (class "Default")
      (node (ref "Q2") (pin "D") (pinfunction "D_D") (pintype "passive"))
      (node (ref "U12") (pin "P$18") (pinfunction "RESET_N_P$18") (pintype "bidirectional"))
    )
    (net (code "98") (name "Net-(U12-V_BCKP)") (class "Default")
      (node (ref "C20") (pin "1") (pinfunction "1_1") (pintype "bidirectional"))
      (node (ref "R25") (pin "2") (pinfunction "2_2") (pintype "passive"))
      (node (ref "U12") (pin "P$2") (pinfunction "V_BCKP_P$2") (pintype "bidirectional"))
    )
    (net (code "99") (name "PPS") (class "Default")
      (node (ref "J1") (pin "7") (pinfunction "PPS_7") (pintype "bidirectional"))
      (node (ref "TP2") (pin "TP") (pinfunction "TP_TP") (pintype "input"))
      (node (ref "U11") (pin "19") (pinfunction "PB04_19") (pintype "bidirectional"))
    )
    (net (code "100") (name "SCL") (class "Default")
      (node (ref "J1") (pin "5") (pinfunction "SCL_5") (pintype "bidirectional"))
      (node (ref "R2") (pin "2") (pinfunction "2_2") (pintype "passive"))
      (node (ref "R4") (pin "2") (pinfunction "2_2") (pintype "passive"))
    )
    (net (code "101") (name "SCLK") (class "Default")
      (node (ref "U1") (pin "16") (pinfunction "SPI_SCK/P00_16") (pintype "bidirectional"))
      (node (ref "U11") (pin "59") (pinfunction "PA23_59") (pintype "bidirectional"))
      (node (ref "U6") (pin "14") (pinfunction "P9_14") (pintype "bidirectional"))
    )
    (net (code "102") (name "SDA") (class "Default")
      (node (ref "J1") (pin "6") (pinfunction "SDA_6") (pintype "bidirectional"))
      (node (ref "R1") (pin "2") (pinfunction "2_2") (pintype "passive"))
      (node (ref "R3") (pin "2") (pinfunction "2_2") (pintype "passive"))
    )
    (net (code "103") (name "USB_D+") (class "Default")
      (node (ref "J1") (pin "11") (pinfunction "USB_D+_11") (pintype "bidirectional"))
      (node (ref "U11") (pin "63") (pinfunction "PA26_63") (pintype "bidirectional"))
    )
    (net (code "104") (name "USB_D-") (class "Default")
      (node (ref "J1") (pin "12") (pinfunction "USB_D-_12") (pintype "bidirectional"))
      (node (ref "U11") (pin "62") (pinfunction "PA25_62") (pintype "bidirectional"))
    )
    (net (code "105") (name "V_GSM_INT") (class "Default")
      (node (ref "R10") (pin "2") (pinfunction "2_2") (pintype "passive"))
      (node (ref "U10") (pin "2") (pinfunction "VCCA_2") (pintype "bidirectional"))
      (node (ref "U12") (pin "P$4") (pinfunction "V_INT_P$4") (pintype "bidirectional"))
    )
    (net (code "106") (name "unconnected-(J1-USB_VBUS-Pad13)") (class "Default")
      (node (ref "J1") (pin "13") (pinfunction "USB_VBUS_13") (pintype "bidirectional"))
    )
    (net (code "107") (name "unconnected-(J2-SWO-Pad6)") (class "Default")
      (node (ref "J2") (pin "6") (pinfunction "SWO_6") (pintype "bidirectional"))
    )
    (net (code "108") (name "unconnected-(J4-C6(VPP)-PadC6)") (class "Default")
      (node (ref "J4") (pin "C6") (pinfunction "C6(VPP)_C6") (pintype "bidirectional"))
    )
    (net (code "109") (name "unconnected-(J5-SWO-Pad6)") (class "Default")
      (node (ref "J5") (pin "6") (pinfunction "SWO_6") (pintype "bidirectional"))
    )
    (net (code "110") (name "unconnected-(U1-BATTERY-Pad31)") (class "Default")
      (node (ref "U1") (pin "31") (pinfunction "BATTERY_31") (pintype "bidirectional"))
    )
    (net (code "111") (name "unconnected-(U1-I2C_SCL-Pad17)") (class "Default")
      (node (ref "U1") (pin "17") (pinfunction "I2C_SCL_17") (pintype "bidirectional"))
    )
    (net (code "112") (name "unconnected-(U1-I2C_SDA-Pad18)") (class "Default")
      (node (ref "U1") (pin "18") (pinfunction "I2C_SDA_18") (pintype "bidirectional"))
    )
    (net (code "113") (name "unconnected-(U1-P02{slash}AIN3-Pad25)") (class "Default")
      (node (ref "U1") (pin "25") (pinfunction "P02/AIN3_25") (pintype "bidirectional"))
    )
    (net (code "114") (name "unconnected-(U1-P03{slash}AIN4-Pad26)") (class "Default")
      (node (ref "U1") (pin "26") (pinfunction "P03/AIN4_26") (pintype "bidirectional"))
    )
    (net (code "115") (name "unconnected-(U1-P04{slash}AIN5-Pad27)") (class "Default")
      (node (ref "U1") (pin "27") (pinfunction "P04/AIN5_27") (pintype "bidirectional"))
    )
    (net (code "116") (name "unconnected-(U1-P05{slash}AIN6-Pad28)") (class "Default")
      (node (ref "U1") (pin "28") (pinfunction "P05/AIN6_28") (pintype "bidirectional"))
    )
    (net (code "117") (name "unconnected-(U1-P17-Pad2)") (class "Default")
      (node (ref "U1") (pin "2") (pinfunction "P17_2") (pintype "bidirectional"))
    )
    (net (code "118") (name "unconnected-(U1-P21-Pad6)") (class "Default")
      (node (ref "U1") (pin "6") (pinfunction "P21_6") (pintype "bidirectional"))
    )
    (net (code "119") (name "unconnected-(U1-P22-Pad7)") (class "Default")
      (node (ref "U1") (pin "7") (pinfunction "P22_7") (pintype "bidirectional"))
    )
    (net (code "120") (name "unconnected-(U1-P23-Pad8)") (class "Default")
      (node (ref "U1") (pin "8") (pinfunction "P23_8") (pintype "bidirectional"))
    )
    (net (code "121") (name "unconnected-(U1-P24-Pad9)") (class "Default")
      (node (ref "U1") (pin "9") (pinfunction "P24_9") (pintype "bidirectional"))
    )
    (net (code "122") (name "unconnected-(U1-PO6{slash}AIN7-Pad29)") (class "Default")
      (node (ref "U1") (pin "29") (pinfunction "PO6/AIN7_29") (pintype "bidirectional"))
    )
    (net (code "123") (name "unconnected-(U1-SWDCLK-Pad4)") (class "Default")
      (node (ref "U1") (pin "4") (pinfunction "SWDCLK_4") (pintype "bidirectional"))
    )
    (net (code "124") (name "unconnected-(U1-SWDIO{slash}~{RESET}-Pad30)") (class "Default")
      (node (ref "U1") (pin "30") (pinfunction "SWDIO/~{RESET}_30") (pintype "bidirectional"))
    )
    (net (code "125") (name "unconnected-(U1-UNUSED-Pad5)") (class "Default")
      (node (ref "U1") (pin "5") (pinfunction "UNUSED_5") (pintype "bidirectional"))
    )
    (net (code "126") (name "unconnected-(U1-UNUSED2-Pad10)") (class "Default")
      (node (ref "U1") (pin "10") (pinfunction "UNUSED2_10") (pintype "bidirectional"))
    )
    (net (code "127") (name "unconnected-(U1-UNUSED3-Pad11)") (class "Default")
      (node (ref "U1") (pin "11") (pinfunction "UNUSED3_11") (pintype "bidirectional"))
    )
    (net (code "128") (name "unconnected-(U1-UNUSED4-Pad12)") (class "Default")
      (node (ref "U1") (pin "12") (pinfunction "UNUSED4_12") (pintype "bidirectional"))
    )
    (net (code "129") (name "unconnected-(U1-UNUSED5-Pad13)") (class "Default")
      (node (ref "U1") (pin "13") (pinfunction "UNUSED5_13") (pintype "bidirectional"))
    )
    (net (code "130") (name "unconnected-(U6-P4-Pad5)") (class "Default")
      (node (ref "U6") (pin "5") (pinfunction "P4_5") (pintype "bidirectional"))
    )
    (net (code "131") (name "unconnected-(U6-P11-Pad20)") (class "Default")
      (node (ref "U6") (pin "20") (pinfunction "P11_20") (pintype "bidirectional"))
    )
    (net (code "132") (name "unconnected-(U6-P14-Pad24)") (class "Default")
      (node (ref "U6") (pin "24") (pinfunction "P14_24") (pintype "bidirectional"))
    )
    (net (code "133") (name "unconnected-(U6-P15-Pad25)") (class "Default")
      (node (ref "U6") (pin "25") (pinfunction "P15_25") (pintype "bidirectional"))
    )
    (net (code "134") (name "unconnected-(U6-P17-Pad29)") (class "Default")
      (node (ref "U6") (pin "29") (pinfunction "P17_29") (pintype "bidirectional"))
    )
    (net (code "135") (name "unconnected-(U7-SC3-Pad16)") (class "Default")
      (node (ref "U7") (pin "16") (pinfunction "SC3_16") (pintype "bidirectional"))
    )
    (net (code "136") (name "unconnected-(U7-SD3-Pad15)") (class "Default")
      (node (ref "U7") (pin "15") (pinfunction "SD3_15") (pintype "bidirectional"))
    )
    (net (code "137") (name "unconnected-(U11-XIN32-Pad17)") (class "Default")
      (node (ref "U11") (pin "17") (pinfunction "XIN32_17") (pintype "bidirectional"))
    )
    (net (code "138") (name "unconnected-(U11-XOUT32-Pad18)") (class "Default")
      (node (ref "U11") (pin "18") (pinfunction "XOUT32_18") (pintype "bidirectional"))
    )
    (net (code "139") (name "unconnected-(U12-ANT_DET-PadP$62)") (class "Default")
      (node (ref "U12") (pin "P$62") (pinfunction "ANT_DET_P$62") (pintype "bidirectional"))
    )
    (net (code "140") (name "unconnected-(U12-DCD-PadP$8)") (class "Default")
      (node (ref "U12") (pin "P$8") (pinfunction "DCD_P$8") (pintype "bidirectional"))
    )
    (net (code "141") (name "unconnected-(U12-DSR-PadP$6)") (class "Default")
      (node (ref "U12") (pin "P$6") (pinfunction "DSR_P$6") (pintype "bidirectional"))
    )
    (net (code "142") (name "unconnected-(U12-GPIO3-PadP$24)") (class "Default")
      (node (ref "U12") (pin "P$24") (pinfunction "GPIO3_P$24") (pintype "bidirectional"))
    )
    (net (code "143") (name "unconnected-(U12-GPIO4-PadP$25)") (class "Default")
      (node (ref "U12") (pin "P$25") (pinfunction "GPIO4_P$25") (pintype "bidirectional"))
    )
    (net (code "144") (name "unconnected-(U12-I2S_CLK-PadP$36)") (class "Default")
      (node (ref "U12") (pin "P$36") (pinfunction "I2S_CLK_P$36") (pintype "bidirectional"))
    )
    (net (code "145") (name "unconnected-(U12-I2S_RXD-PadP$37)") (class "Default")
      (node (ref "U12") (pin "P$37") (pinfunction "I2S_RXD_P$37") (pintype "bidirectional"))
    )
    (net (code "146") (name "unconnected-(U12-I2S_TXD-PadP$35)") (class "Default")
      (node (ref "U12") (pin "P$35") (pinfunction "I2S_TXD_P$35") (pintype "bidirectional"))
    )
    (net (code "147") (name "unconnected-(U12-I2S_WA-PadP$34)") (class "Default")
      (node (ref "U12") (pin "P$34") (pinfunction "I2S_WA_P$34") (pintype "bidirectional"))
    )
    (net (code "148") (name "unconnected-(U12-MIC_BIAS-PadP$46)") (class "Default")
      (node (ref "U12") (pin "P$46") (pinfunction "MIC_BIAS_P$46") (pintype "bidirectional"))
    )
    (net (code "149") (name "unconnected-(U12-MIC_GND-PadP$47)") (class "Default")
      (node (ref "U12") (pin "P$47") (pinfunction "MIC_GND_P$47") (pintype "bidirectional"))
    )
    (net (code "150") (name "unconnected-(U12-MIC_N-PadP$48)") (class "Default")
      (node (ref "U12") (pin "P$48") (pinfunction "MIC_N_P$48") (pintype "bidirectional"))
    )
    (net (code "151") (name "unconnected-(U12-MIC_P-PadP$49)") (class "Default")
      (node (ref "U12") (pin "P$49") (pinfunction "MIC_P_P$49") (pintype "bidirectional"))
    )
    (net (code "152") (name "unconnected-(U12-RI-PadP$7)") (class "Default")
      (node (ref "U12") (pin "P$7") (pinfunction "RI_P$7") (pintype "bidirectional"))
    )
    (net (code "153") (name "unconnected-(U12-SCL-PadP$27)") (class "Default")
      (node (ref "U12") (pin "P$27") (pinfunction "SCL_P$27") (pintype "bidirectional"))
    )
    (net (code "154") (name "unconnected-(U12-SDA-PadP$26)") (class "Default")
      (node (ref "U12") (pin "P$26") (pinfunction "SDA_P$26") (pintype "bidirectional"))
    )
    (net (code "155") (name "unconnected-(U12-SIM_DET-PadP$42)") (class "Default")
      (node (ref "U12") (pin "P$42") (pinfunction "SIM_DET_P$42") (pintype "bidirectional"))
    )
    (net (code "156") (name "unconnected-(U12-SPK_N-PadP$45)") (class "Default")
      (node (ref "U12") (pin "P$45") (pinfunction "SPK_N_P$45") (pintype "bidirectional"))
    )
    (net (code "157") (name "unconnected-(U12-SPK_P-PadP$44)") (class "Default")
      (node (ref "U12") (pin "P$44") (pinfunction "SPK_P_P$44") (pintype "bidirectional"))
    )
    (net (code "158") (name "~{CONTROLLER_RESET}") (class "Default")
      (node (ref "J5") (pin "3") (pinfunction "~{RESET}_3") (pintype "bidirectional"))
      (node (ref "U11") (pin "4") (pinfunction "~{RESET}_4") (pintype "bidirectional"))
    )
    (net (code "159") (name "~{GSM_RST}") (class "Default")
      (node (ref "Q2") (pin "G") (pinfunction "G_G") (pintype "passive"))
      (node (ref "TP7") (pin "TP") (pinfunction "TP_TP") (pintype "input"))
      (node (ref "U11") (pin "40") (pinfunction "PA13_40") (pintype "bidirectional"))
    )
    (net (code "160") (name "~{IM880_RESET}") (class "Default")
      (node (ref "J2") (pin "3") (pinfunction "~{RESET}_3") (pintype "bidirectional"))
      (node (ref "U11") (pin "44") (pinfunction "PA17_44") (pintype "bidirectional"))
      (node (ref "U6") (pin "7") (pinfunction "~{RESET}_7") (pintype "bidirectional"))
    )
    (net (code "161") (name "~{NUCLEUM_RESET}") (class "Default")
      (node (ref "U1") (pin "3") (pinfunction "SWDIO/~{RESET}_3") (pintype "bidirectional"))
      (node (ref "U11") (pin "13") (pinfunction "PB02_13") (pintype "bidirectional"))
    )
  )
)
